# C-metr_analog.net
KiCad netlist of a schematic drawn in Altium Designer
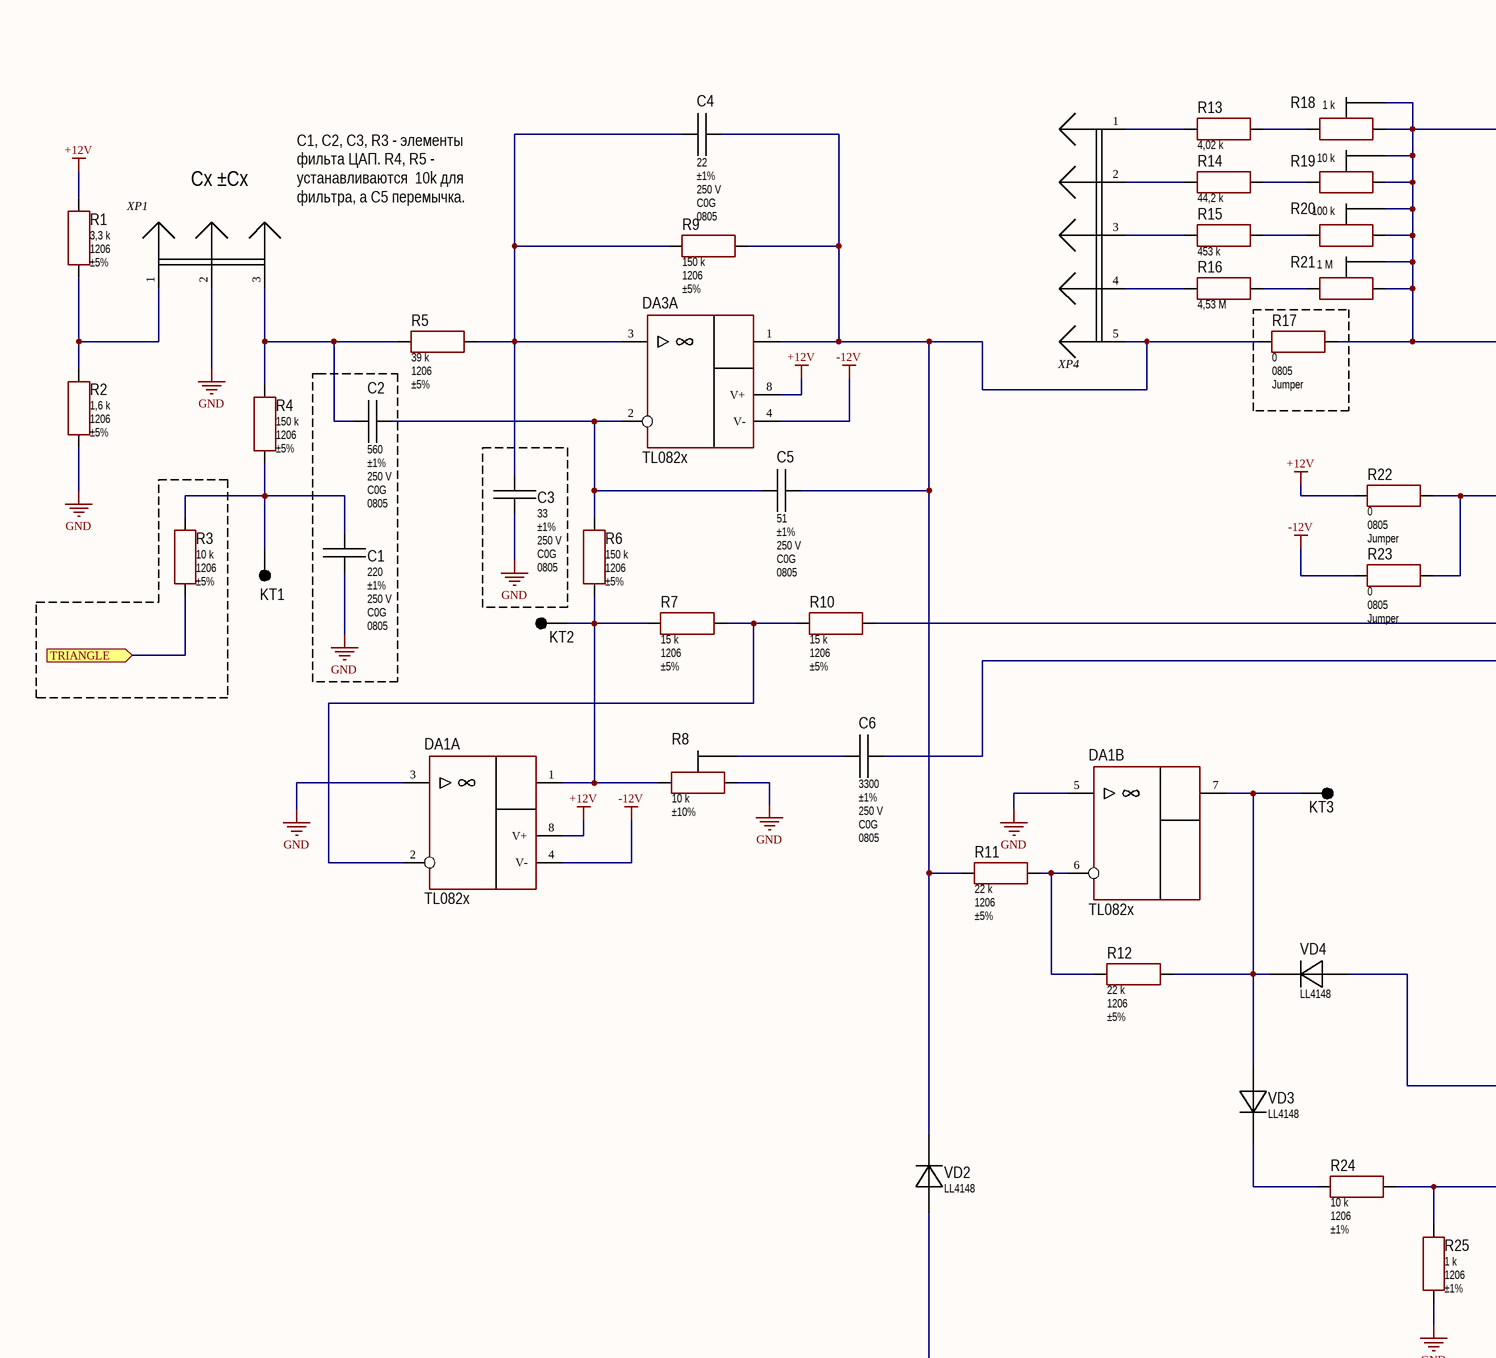
[diagram p0: C-metr_analog.SchDoc, top left]
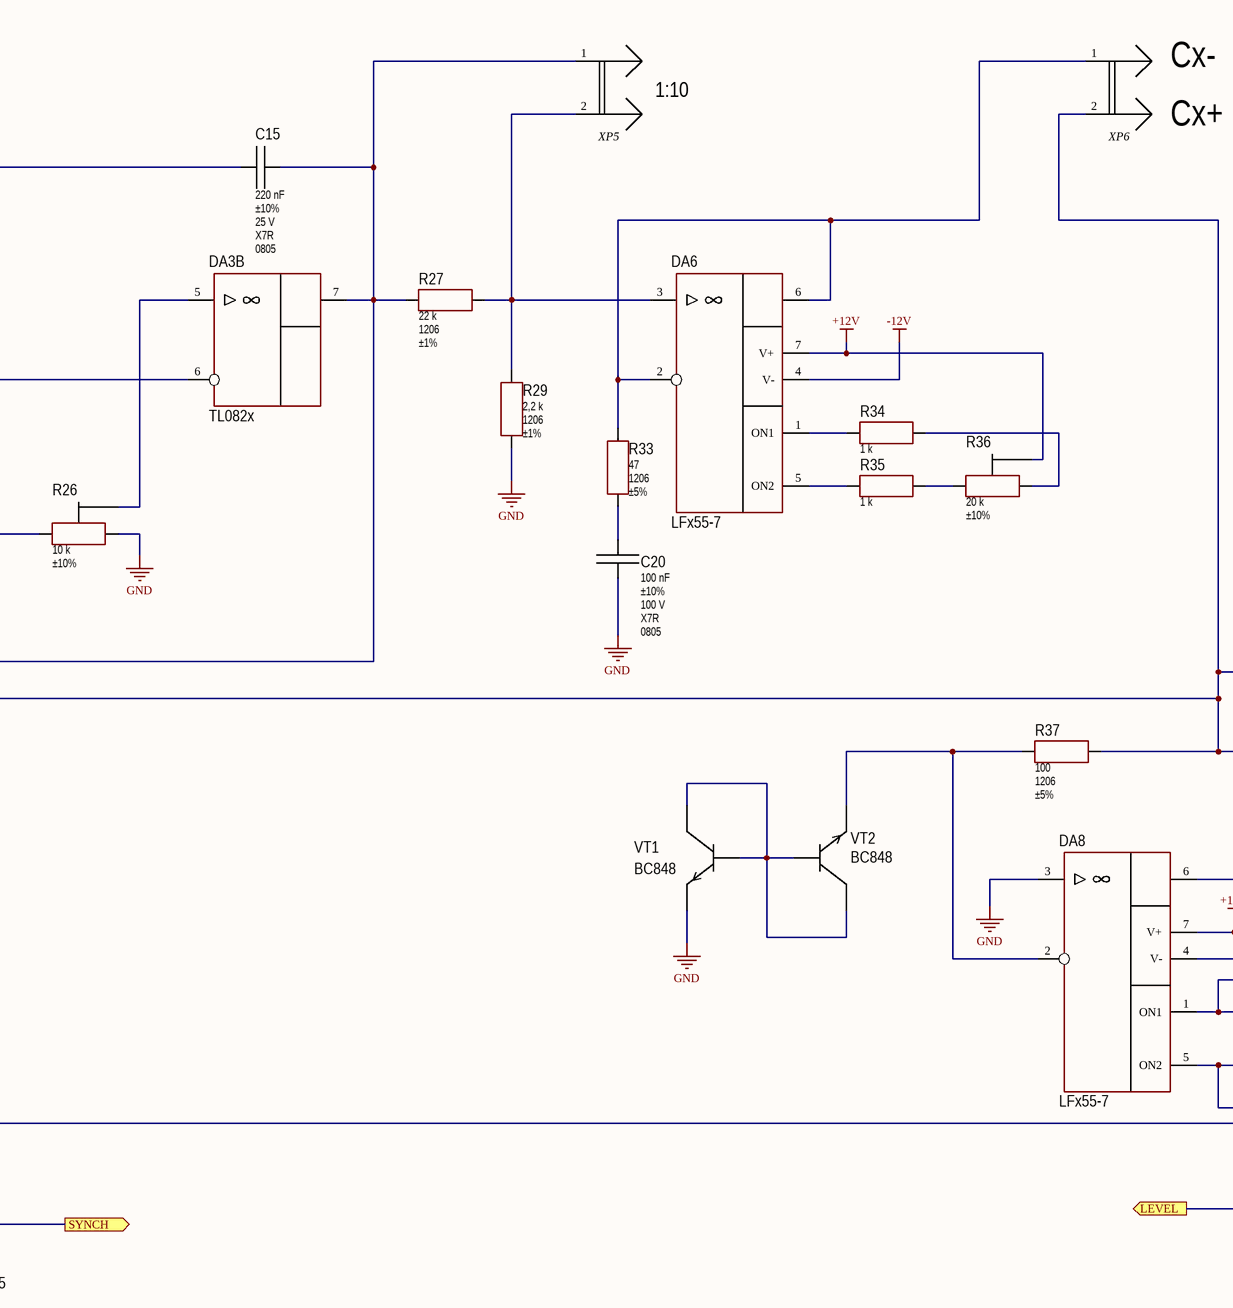
[diagram p1: C-metr_analog.SchDoc, top middle]
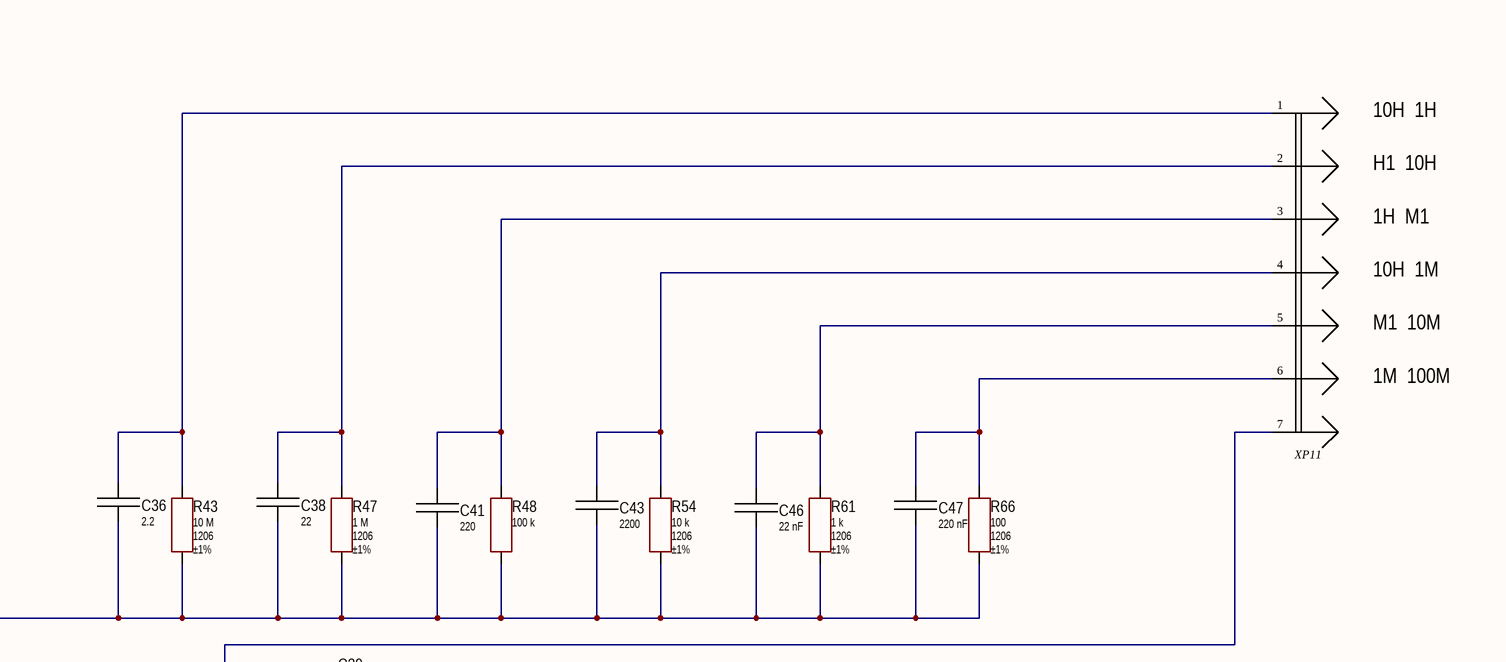
[diagram p2: C-metr_analog.SchDoc, top right]
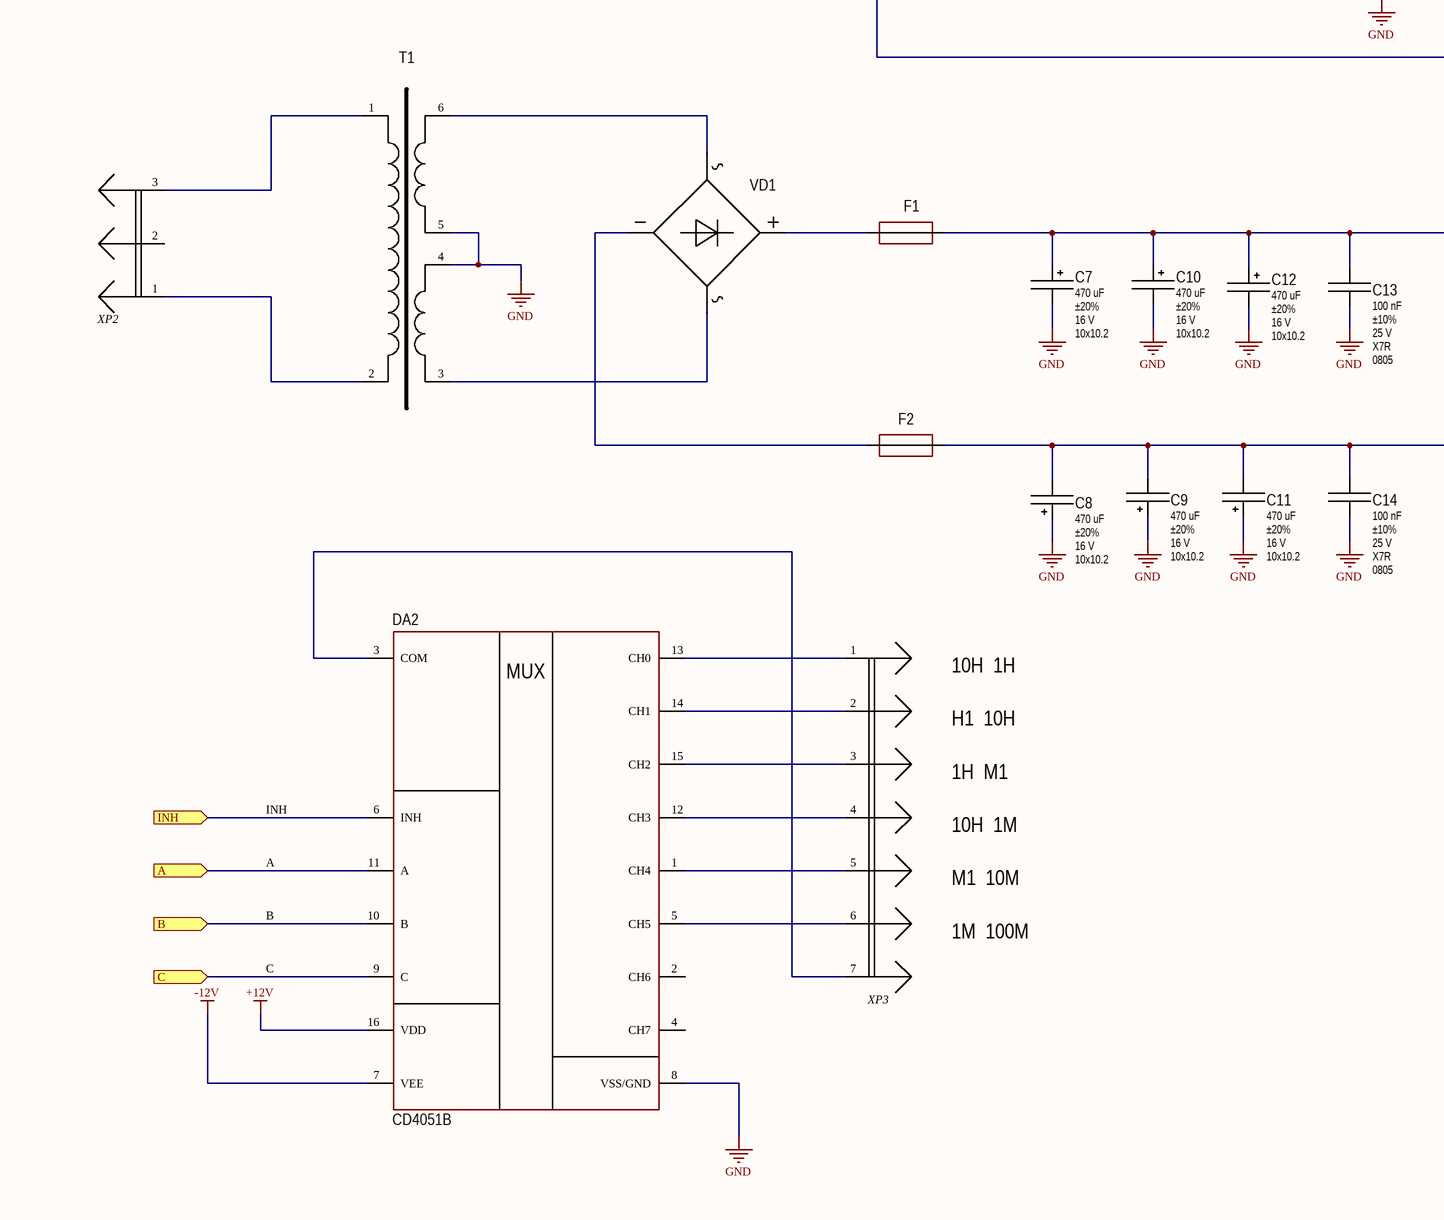
[diagram p3: C-metr_analog.SchDoc, bottom left]
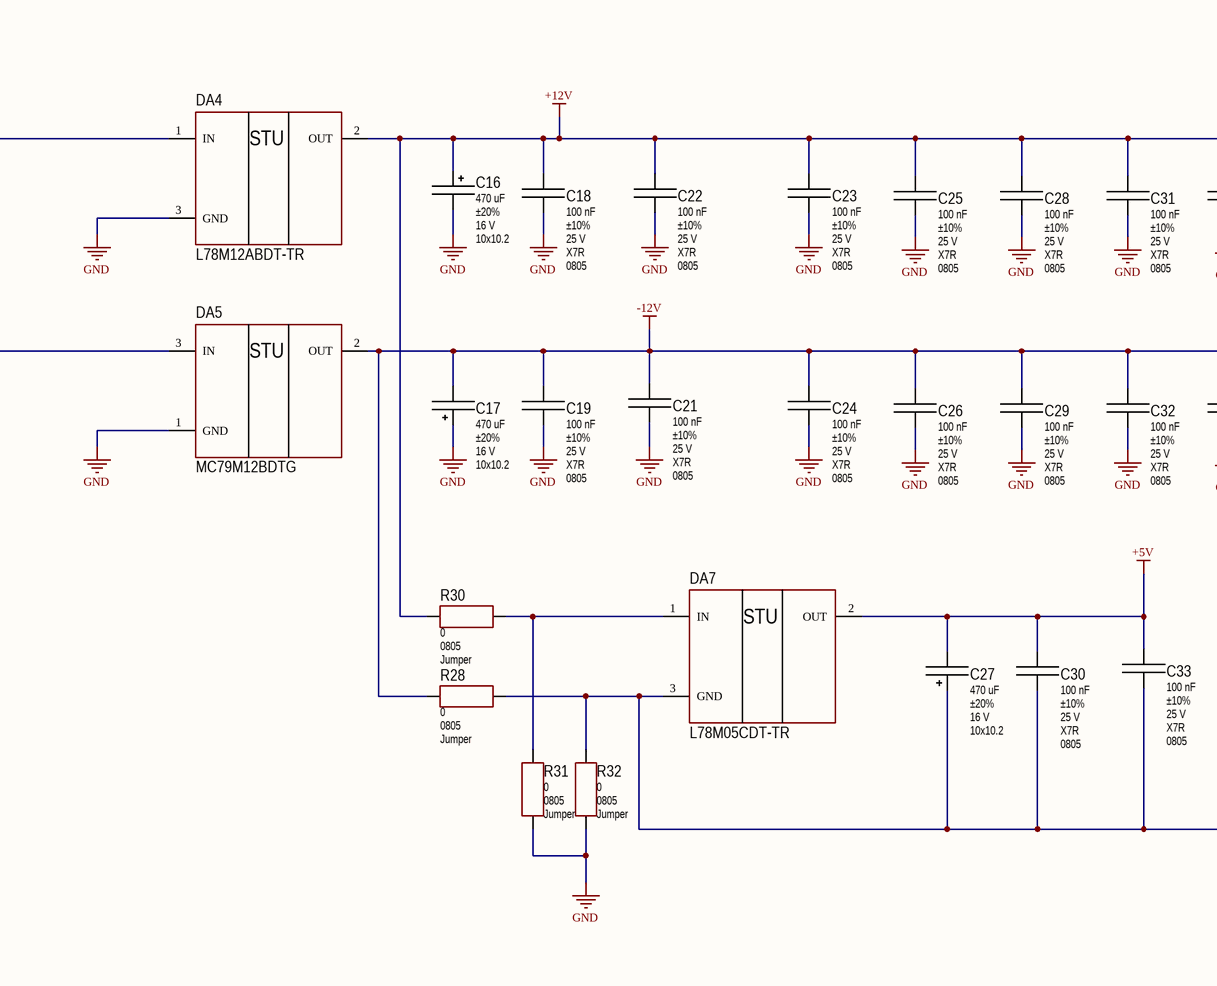
[diagram p4: C-metr_analog.SchDoc, bottom middle]
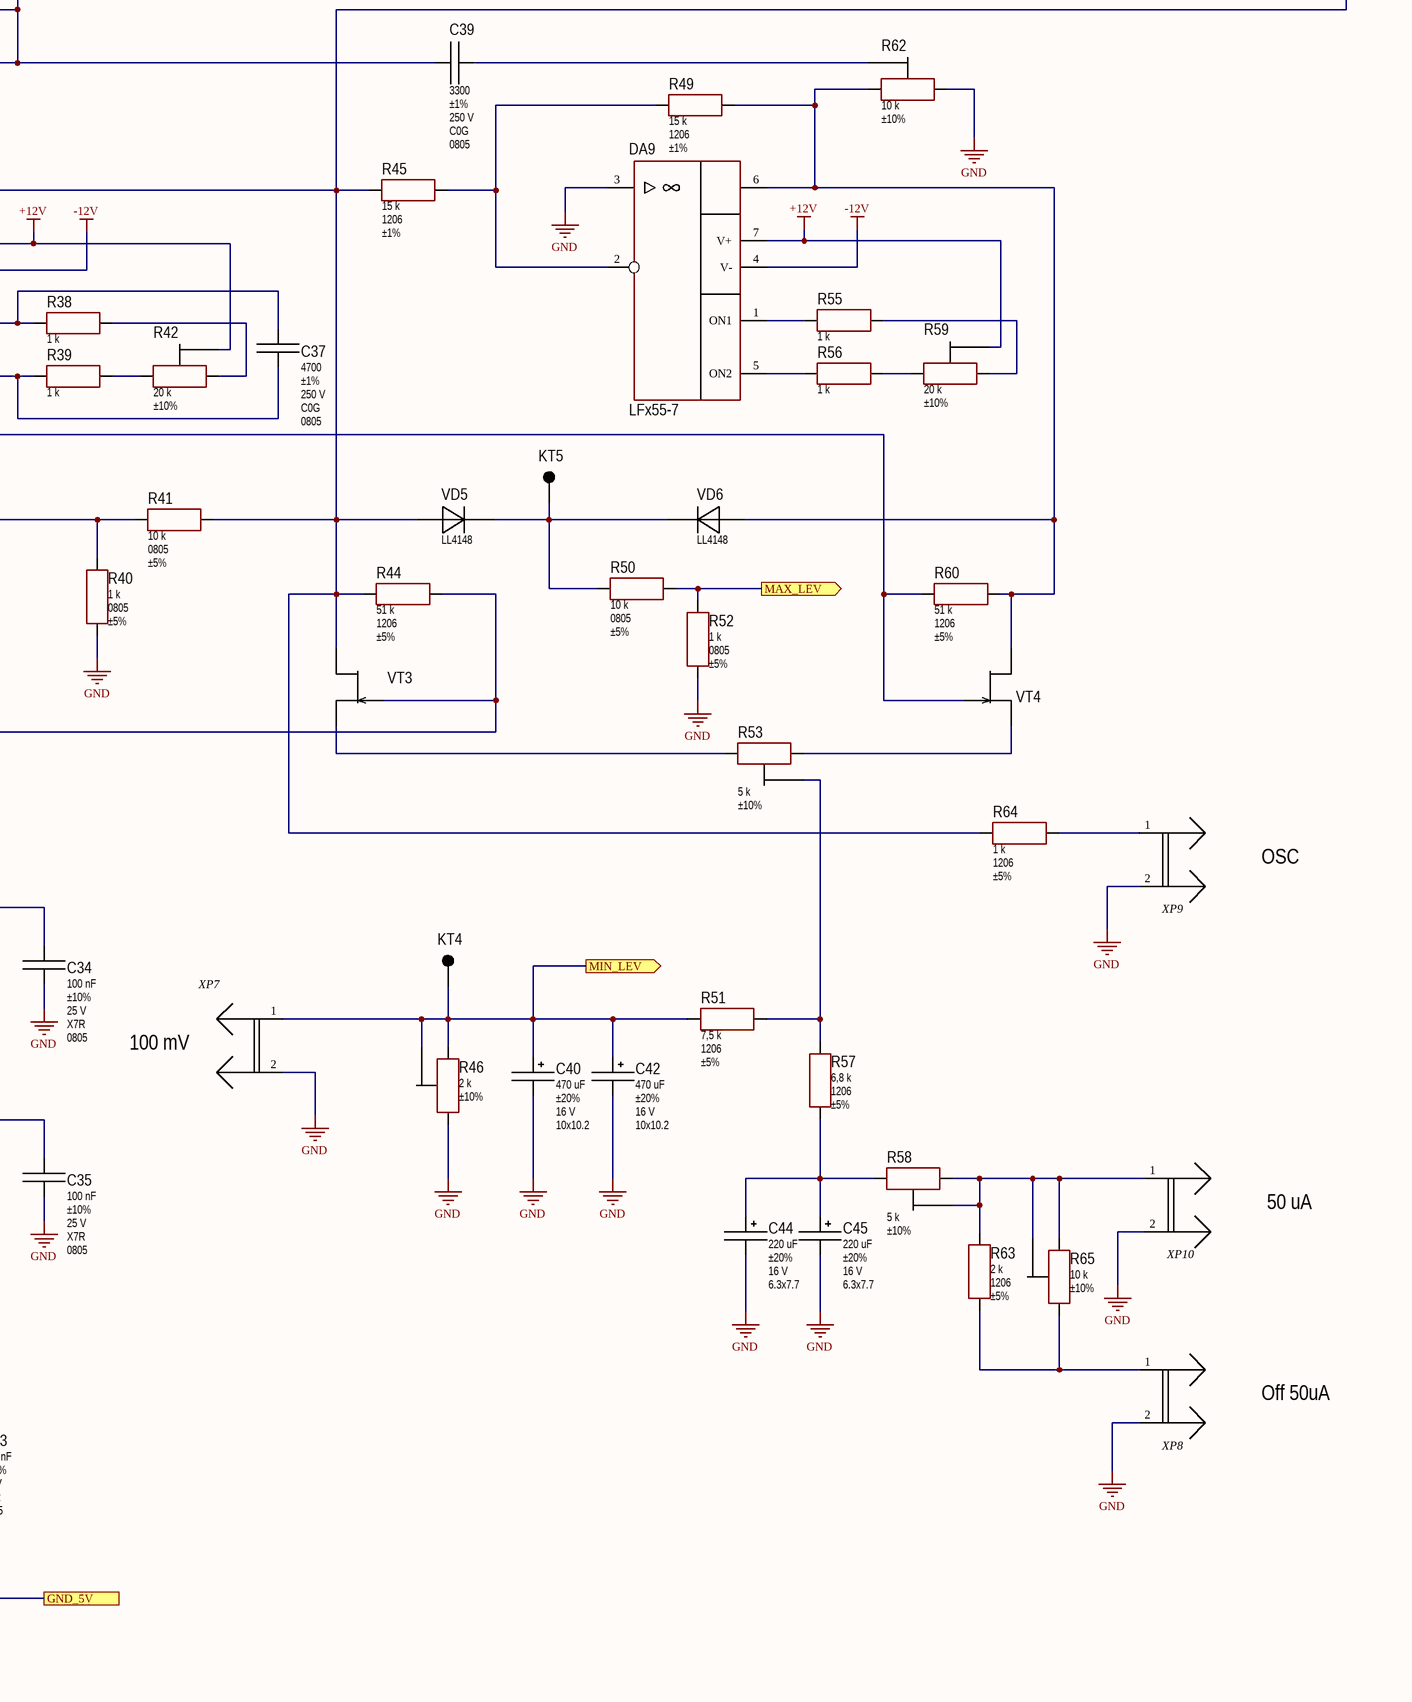
[diagram p5: C-metr_analog.SchDoc, bottom right]

(export (version "E")
  (design (tool "Eeschema 10.0.6"))
  (components
    (comp (ref "C1")
      (value "220")
      (footprint "C-0805-1.0")
      (fields
        (field (name "VALUESCH") "220")
        (field (name "TOLERANCE") "±1%")
        (field (name "VOLTAGE") "250 V")
        (field (name "DIELECTRIC") "C0G")
        (field (name "CASE") "0805")
        (field (name "PART NUMBER") "GRM21A5C2E221FW01D")
        (field (name "MANUFACTURER") "Murata Electronics")
      )
      (libsource (lib "GOST") (part "Capacitor"))
    )
    (comp (ref "C2")
      (value "560")
      (footprint "C-0805-1.0")
      (fields
        (field (name "VALUESCH") "560")
        (field (name "TOLERANCE") "±1%")
        (field (name "VOLTAGE") "250 V")
        (field (name "DIELECTRIC") "C0G")
        (field (name "CASE") "0805")
        (field (name "PART NUMBER") "GRM21A5C2E561FW01D")
        (field (name "MANUFACTURER") "Murata Electronics")
      )
      (libsource (lib "GOST") (part "Capacitor"))
    )
    (comp (ref "C3")
      (value "33")
      (footprint "C-0805-1.0")
      (fields
        (field (name "VALUESCH") "33")
        (field (name "TOLERANCE") "±1%")
        (field (name "VOLTAGE") "250 V")
        (field (name "DIELECTRIC") "C0G")
        (field (name "CASE") "0805")
        (field (name "PART NUMBER") "GRM21A5C2E330FW01D")
        (field (name "MANUFACTURER") "Murata Electronics")
      )
      (libsource (lib "GOST") (part "Capacitor"))
    )
    (comp (ref "C4")
      (value "22")
      (footprint "C-0805-1.0")
      (fields
        (field (name "VALUESCH") "22")
        (field (name "TOLERANCE") "±1%")
        (field (name "VOLTAGE") "250 V")
        (field (name "DIELECTRIC") "C0G")
        (field (name "CASE") "0805")
        (field (name "PART NUMBER") "GRM21A5C2E220FW01D")
        (field (name "MANUFACTURER") "Murata Electronics")
      )
      (libsource (lib "GOST") (part "Capacitor"))
    )
    (comp (ref "C5")
      (value "51")
      (footprint "C-0805-1.0")
      (fields
        (field (name "VALUESCH") "51")
        (field (name "TOLERANCE") "±1%")
        (field (name "VOLTAGE") "250 V")
        (field (name "DIELECTRIC") "C0G")
        (field (name "CASE") "0805")
        (field (name "PART NUMBER") "GRM21A5C2E151FW01D")
        (field (name "MANUFACTURER") "Murata Electronics")
      )
      (libsource (lib "GOST") (part "Capacitor"))
    )
    (comp (ref "C6")
      (value "3300")
      (footprint "C-0805-1.25")
      (fields
        (field (name "VALUESCH") "3300")
        (field (name "TOLERANCE") "±1%")
        (field (name "VOLTAGE") "250 V")
        (field (name "DIELECTRIC") "C0G")
        (field (name "CASE") "0805")
        (field (name "PART NUMBER") "GRM21B5C2E332FW01D")
        (field (name "MANUFACTURER") "Murata Electronics")
      )
      (libsource (lib "GOST") (part "Capacitor"))
    )
    (comp (ref "C7")
      (value "470 uF")
      (footprint "CAP-CASE G")
      (fields
        (field (name "TOLERANCE") "±20%")
        (field (name "VOLTAGE") "16 V")
        (field (name "CASE") "10x10.2")
        (field (name "PART NUMBER") "EEE-1CA471P")
        (field (name "MANUFACTURER") "Panasonic Electronic Components")
      )
      (libsource (lib "GOST") (part "Capacitor Polar"))
    )
    (comp (ref "C8")
      (value "470 uF")
      (footprint "CAP-CASE G")
      (fields
        (field (name "TOLERANCE") "±20%")
        (field (name "VOLTAGE") "16 V")
        (field (name "CASE") "10x10.2")
        (field (name "PART NUMBER") "EEE-1CA471P")
        (field (name "MANUFACTURER") "Panasonic Electronic Components")
      )
      (libsource (lib "GOST") (part "Capacitor Polar"))
    )
    (comp (ref "C9")
      (value "470 uF")
      (footprint "CAP-CASE G")
      (fields
        (field (name "TOLERANCE") "±20%")
        (field (name "VOLTAGE") "16 V")
        (field (name "CASE") "10x10.2")
        (field (name "PART NUMBER") "EEE-1CA471P")
        (field (name "MANUFACTURER") "Panasonic Electronic Components")
      )
      (libsource (lib "GOST") (part "Capacitor Polar"))
    )
    (comp (ref "C10")
      (value "470 uF")
      (footprint "CAP-CASE G")
      (fields
        (field (name "TOLERANCE") "±20%")
        (field (name "VOLTAGE") "16 V")
        (field (name "CASE") "10x10.2")
        (field (name "PART NUMBER") "EEE-1CA471P")
        (field (name "MANUFACTURER") "Panasonic Electronic Components")
      )
      (libsource (lib "GOST") (part "Capacitor Polar"))
    )
    (comp (ref "C11")
      (value "470 uF")
      (footprint "CAP-CASE G")
      (fields
        (field (name "TOLERANCE") "±20%")
        (field (name "VOLTAGE") "16 V")
        (field (name "CASE") "10x10.2")
        (field (name "PART NUMBER") "EEE-1CA471P")
        (field (name "MANUFACTURER") "Panasonic Electronic Components")
      )
      (libsource (lib "GOST") (part "Capacitor Polar"))
    )
    (comp (ref "C12")
      (value "470 uF")
      (footprint "CAP-CASE G")
      (fields
        (field (name "TOLERANCE") "±20%")
        (field (name "VOLTAGE") "16 V")
        (field (name "CASE") "10x10.2")
        (field (name "PART NUMBER") "EEE-1CA471P")
        (field (name "MANUFACTURER") "Panasonic Electronic Components")
      )
      (libsource (lib "GOST") (part "Capacitor Polar"))
    )
    (comp (ref "C13")
      (value "100 nF")
      (footprint "C-0805-0.95")
      (fields
        (field (name "VALUESCH") "100 nF")
        (field (name "TOLERANCE") "±10%")
        (field (name "VOLTAGE") "25 V")
        (field (name "DIELECTRIC") "X7R")
        (field (name "CASE") "0805")
        (field (name "PART NUMBER") "CC0805KRX7R8BB104")
        (field (name "MANUFACTURER") "Yageo")
      )
      (libsource (lib "GOST") (part "Capacitor"))
    )
    (comp (ref "C14")
      (value "100 nF")
      (footprint "C-0805-0.95")
      (fields
        (field (name "VALUESCH") "100 nF")
        (field (name "TOLERANCE") "±10%")
        (field (name "VOLTAGE") "25 V")
        (field (name "DIELECTRIC") "X7R")
        (field (name "CASE") "0805")
        (field (name "PART NUMBER") "CC0805KRX7R8BB104")
        (field (name "MANUFACTURER") "Yageo")
      )
      (libsource (lib "GOST") (part "Capacitor"))
    )
    (comp (ref "C15")
      (value "220 nF")
      (footprint "C-0805-0.95")
      (fields
        (field (name "VALUESCH") "220 nF")
        (field (name "TOLERANCE") "±10%")
        (field (name "VOLTAGE") "25 V")
        (field (name "DIELECTRIC") "X7R")
        (field (name "CASE") "0805")
        (field (name "PART NUMBER") "CC0805KRX7R8BB224")
        (field (name "MANUFACTURER") "Yageo")
      )
      (libsource (lib "GOST") (part "Capacitor"))
    )
    (comp (ref "C16")
      (value "470 uF")
      (footprint "CAP-CASE G")
      (fields
        (field (name "TOLERANCE") "±20%")
        (field (name "VOLTAGE") "16 V")
        (field (name "CASE") "10x10.2")
        (field (name "PART NUMBER") "EEE-1CA471P")
        (field (name "MANUFACTURER") "Panasonic Electronic Components")
      )
      (libsource (lib "GOST") (part "Capacitor Polar"))
    )
    (comp (ref "C17")
      (value "470 uF")
      (footprint "CAP-CASE G")
      (fields
        (field (name "TOLERANCE") "±20%")
        (field (name "VOLTAGE") "16 V")
        (field (name "CASE") "10x10.2")
        (field (name "PART NUMBER") "EEE-1CA471P")
        (field (name "MANUFACTURER") "Panasonic Electronic Components")
      )
      (libsource (lib "GOST") (part "Capacitor Polar"))
    )
    (comp (ref "C18")
      (value "100 nF")
      (footprint "C-0805-0.95")
      (fields
        (field (name "VALUESCH") "100 nF")
        (field (name "TOLERANCE") "±10%")
        (field (name "VOLTAGE") "25 V")
        (field (name "DIELECTRIC") "X7R")
        (field (name "CASE") "0805")
        (field (name "PART NUMBER") "CC0805KRX7R8BB104")
        (field (name "MANUFACTURER") "Yageo")
      )
      (libsource (lib "GOST") (part "Capacitor"))
    )
    (comp (ref "C19")
      (value "100 nF")
      (footprint "C-0805-0.95")
      (fields
        (field (name "VALUESCH") "100 nF")
        (field (name "TOLERANCE") "±10%")
        (field (name "VOLTAGE") "25 V")
        (field (name "DIELECTRIC") "X7R")
        (field (name "CASE") "0805")
        (field (name "PART NUMBER") "CC0805KRX7R8BB104")
        (field (name "MANUFACTURER") "Yageo")
      )
      (libsource (lib "GOST") (part "Capacitor"))
    )
    (comp (ref "C20")
      (value "100 nF")
      (footprint "C-0805-1.25")
      (fields
        (field (name "VALUESCH") "100 nF")
        (field (name "TOLERANCE") "±10%")
        (field (name "VOLTAGE") "100 V")
        (field (name "DIELECTRIC") "X7R")
        (field (name "CASE") "0805")
        (field (name "PART NUMBER") "GCM21BR72A104KA37L")
        (field (name "MANUFACTURER") "Murata Electronics")
      )
      (libsource (lib "GOST") (part "Capacitor"))
    )
    (comp (ref "C21")
      (value "100 nF")
      (footprint "C-0805-0.95")
      (fields
        (field (name "VALUESCH") "100 nF")
        (field (name "TOLERANCE") "±10%")
        (field (name "VOLTAGE") "25 V")
        (field (name "DIELECTRIC") "X7R")
        (field (name "CASE") "0805")
        (field (name "PART NUMBER") "CC0805KRX7R8BB104")
        (field (name "MANUFACTURER") "Yageo")
      )
      (libsource (lib "GOST") (part "Capacitor"))
    )
    (comp (ref "C22")
      (value "100 nF")
      (footprint "C-0805-0.95")
      (fields
        (field (name "VALUESCH") "100 nF")
        (field (name "TOLERANCE") "±10%")
        (field (name "VOLTAGE") "25 V")
        (field (name "DIELECTRIC") "X7R")
        (field (name "CASE") "0805")
        (field (name "PART NUMBER") "CC0805KRX7R8BB104")
        (field (name "MANUFACTURER") "Yageo")
      )
      (libsource (lib "GOST") (part "Capacitor"))
    )
    (comp (ref "C23")
      (value "100 nF")
      (footprint "C-0805-0.95")
      (fields
        (field (name "VALUESCH") "100 nF")
        (field (name "TOLERANCE") "±10%")
        (field (name "VOLTAGE") "25 V")
        (field (name "DIELECTRIC") "X7R")
        (field (name "CASE") "0805")
        (field (name "PART NUMBER") "CC0805KRX7R8BB104")
        (field (name "MANUFACTURER") "Yageo")
      )
      (libsource (lib "GOST") (part "Capacitor"))
    )
    (comp (ref "C24")
      (value "100 nF")
      (footprint "C-0805-0.95")
      (fields
        (field (name "VALUESCH") "100 nF")
        (field (name "TOLERANCE") "±10%")
        (field (name "VOLTAGE") "25 V")
        (field (name "DIELECTRIC") "X7R")
        (field (name "CASE") "0805")
        (field (name "PART NUMBER") "CC0805KRX7R8BB104")
        (field (name "MANUFACTURER") "Yageo")
      )
      (libsource (lib "GOST") (part "Capacitor"))
    )
    (comp (ref "C25")
      (value "100 nF")
      (footprint "C-0805-0.95")
      (fields
        (field (name "VALUESCH") "100 nF")
        (field (name "TOLERANCE") "±10%")
        (field (name "VOLTAGE") "25 V")
        (field (name "DIELECTRIC") "X7R")
        (field (name "CASE") "0805")
        (field (name "PART NUMBER") "CC0805KRX7R8BB104")
        (field (name "MANUFACTURER") "Yageo")
      )
      (libsource (lib "GOST") (part "Capacitor"))
    )
    (comp (ref "C26")
      (value "100 nF")
      (footprint "C-0805-0.95")
      (fields
        (field (name "VALUESCH") "100 nF")
        (field (name "TOLERANCE") "±10%")
        (field (name "VOLTAGE") "25 V")
        (field (name "DIELECTRIC") "X7R")
        (field (name "CASE") "0805")
        (field (name "PART NUMBER") "CC0805KRX7R8BB104")
        (field (name "MANUFACTURER") "Yageo")
      )
      (libsource (lib "GOST") (part "Capacitor"))
    )
    (comp (ref "C27")
      (value "470 uF")
      (footprint "CAP-CASE G")
      (fields
        (field (name "TOLERANCE") "±20%")
        (field (name "VOLTAGE") "16 V")
        (field (name "CASE") "10x10.2")
        (field (name "PART NUMBER") "EEE-1CA471P")
        (field (name "MANUFACTURER") "Panasonic Electronic Components")
      )
      (libsource (lib "GOST") (part "Capacitor Polar"))
    )
    (comp (ref "C28")
      (value "100 nF")
      (footprint "C-0805-0.95")
      (fields
        (field (name "VALUESCH") "100 nF")
        (field (name "TOLERANCE") "±10%")
        (field (name "VOLTAGE") "25 V")
        (field (name "DIELECTRIC") "X7R")
        (field (name "CASE") "0805")
        (field (name "PART NUMBER") "CC0805KRX7R8BB104")
        (field (name "MANUFACTURER") "Yageo")
      )
      (libsource (lib "GOST") (part "Capacitor"))
    )
    (comp (ref "C29")
      (value "100 nF")
      (footprint "C-0805-0.95")
      (fields
        (field (name "VALUESCH") "100 nF")
        (field (name "TOLERANCE") "±10%")
        (field (name "VOLTAGE") "25 V")
        (field (name "DIELECTRIC") "X7R")
        (field (name "CASE") "0805")
        (field (name "PART NUMBER") "CC0805KRX7R8BB104")
        (field (name "MANUFACTURER") "Yageo")
      )
      (libsource (lib "GOST") (part "Capacitor"))
    )
    (comp (ref "C30")
      (value "100 nF")
      (footprint "C-0805-0.95")
      (fields
        (field (name "VALUESCH") "100 nF")
        (field (name "TOLERANCE") "±10%")
        (field (name "VOLTAGE") "25 V")
        (field (name "DIELECTRIC") "X7R")
        (field (name "CASE") "0805")
        (field (name "PART NUMBER") "CC0805KRX7R8BB104")
        (field (name "MANUFACTURER") "Yageo")
      )
      (libsource (lib "GOST") (part "Capacitor"))
    )
    (comp (ref "C31")
      (value "100 nF")
      (footprint "C-0805-0.95")
      (fields
        (field (name "VALUESCH") "100 nF")
        (field (name "TOLERANCE") "±10%")
        (field (name "VOLTAGE") "25 V")
        (field (name "DIELECTRIC") "X7R")
        (field (name "CASE") "0805")
        (field (name "PART NUMBER") "CC0805KRX7R8BB104")
        (field (name "MANUFACTURER") "Yageo")
      )
      (libsource (lib "GOST") (part "Capacitor"))
    )
    (comp (ref "C32")
      (value "100 nF")
      (footprint "C-0805-0.95")
      (fields
        (field (name "VALUESCH") "100 nF")
        (field (name "TOLERANCE") "±10%")
        (field (name "VOLTAGE") "25 V")
        (field (name "DIELECTRIC") "X7R")
        (field (name "CASE") "0805")
        (field (name "PART NUMBER") "CC0805KRX7R8BB104")
        (field (name "MANUFACTURER") "Yageo")
      )
      (libsource (lib "GOST") (part "Capacitor"))
    )
    (comp (ref "C33")
      (value "100 nF")
      (footprint "C-0805-0.95")
      (fields
        (field (name "VALUESCH") "100 nF")
        (field (name "TOLERANCE") "±10%")
        (field (name "VOLTAGE") "25 V")
        (field (name "DIELECTRIC") "X7R")
        (field (name "CASE") "0805")
        (field (name "PART NUMBER") "CC0805KRX7R8BB104")
        (field (name "MANUFACTURER") "Yageo")
      )
      (libsource (lib "GOST") (part "Capacitor"))
    )
    (comp (ref "C34")
      (value "100 nF")
      (footprint "C-0805-0.95")
      (fields
        (field (name "VALUESCH") "100 nF")
        (field (name "TOLERANCE") "±10%")
        (field (name "VOLTAGE") "25 V")
        (field (name "DIELECTRIC") "X7R")
        (field (name "CASE") "0805")
        (field (name "PART NUMBER") "CC0805KRX7R8BB104")
        (field (name "MANUFACTURER") "Yageo")
      )
      (libsource (lib "GOST") (part "Capacitor"))
    )
    (comp (ref "C35")
      (value "100 nF")
      (footprint "C-0805-0.95")
      (fields
        (field (name "VALUESCH") "100 nF")
        (field (name "TOLERANCE") "±10%")
        (field (name "VOLTAGE") "25 V")
        (field (name "DIELECTRIC") "X7R")
        (field (name "CASE") "0805")
        (field (name "PART NUMBER") "CC0805KRX7R8BB104")
        (field (name "MANUFACTURER") "Yageo")
      )
      (libsource (lib "GOST") (part "Capacitor"))
    )
    (comp (ref "C36")
      (value "2.2")
      (footprint "C-0805-1.0")
      (fields
        (field (name "VALUESCH") "2.2")
        (field (name "TOLERANCE") "±1%")
        (field (name "VOLTAGE") "250 V")
        (field (name "PART NUMBER") "GRM21A5C2E220FW01D")
      )
      (libsource (lib "GOST") (part "Capacitor"))
    )
    (comp (ref "C37")
      (value "4700")
      (footprint "C-0805-1.25")
      (fields
        (field (name "VALUESCH") "4700")
        (field (name "TOLERANCE") "±1%")
        (field (name "VOLTAGE") "250 V")
        (field (name "DIELECTRIC") "C0G")
        (field (name "CASE") "0805")
        (field (name "PART NUMBER") "GRM21B5C2E472FW01D")
        (field (name "MANUFACTURER") "Murata Electronics")
      )
      (libsource (lib "GOST") (part "Capacitor"))
    )
    (comp (ref "C38")
      (value "22")
      (footprint "C-0805-1.0")
      (fields
        (field (name "VALUESCH") "22")
        (field (name "TOLERANCE") "±1%")
        (field (name "VOLTAGE") "250 V")
        (field (name "PART NUMBER") "GRM21A5C2E220FW01D")
      )
      (libsource (lib "GOST") (part "Capacitor"))
    )
    (comp (ref "C39")
      (value "3300")
      (footprint "C-0805-1.25")
      (fields
        (field (name "VALUESCH") "3300")
        (field (name "TOLERANCE") "±1%")
        (field (name "VOLTAGE") "250 V")
        (field (name "DIELECTRIC") "C0G")
        (field (name "CASE") "0805")
        (field (name "PART NUMBER") "GRM21B5C2E332FW01D")
        (field (name "MANUFACTURER") "Murata Electronics")
      )
      (libsource (lib "GOST") (part "Capacitor"))
    )
    (comp (ref "C40")
      (value "470 uF")
      (footprint "CAP-CASE G")
      (fields
        (field (name "TOLERANCE") "±20%")
        (field (name "VOLTAGE") "16 V")
        (field (name "CASE") "10x10.2")
        (field (name "PART NUMBER") "EEE-1CA471P")
        (field (name "MANUFACTURER") "Panasonic Electronic Components")
      )
      (libsource (lib "GOST") (part "Capacitor Polar"))
    )
    (comp (ref "C41")
      (value "220")
      (footprint "C-0805-1.0")
      (fields
        (field (name "VALUESCH") "220")
        (field (name "TOLERANCE") "±1%")
        (field (name "VOLTAGE") "250 V")
        (field (name "PART NUMBER") "GRM21A5C2E221FW01D")
      )
      (libsource (lib "GOST") (part "Capacitor"))
    )
    (comp (ref "C42")
      (value "470 uF")
      (footprint "CAP-CASE G")
      (fields
        (field (name "TOLERANCE") "±20%")
        (field (name "VOLTAGE") "16 V")
        (field (name "CASE") "10x10.2")
        (field (name "PART NUMBER") "EEE-1CA471P")
        (field (name "MANUFACTURER") "Panasonic Electronic Components")
      )
      (libsource (lib "GOST") (part "Capacitor Polar"))
    )
    (comp (ref "C43")
      (value "2200")
      (footprint "C-0805-1.0")
      (fields
        (field (name "VALUESCH") "2200")
        (field (name "TOLERANCE") "±1%")
        (field (name "VOLTAGE") "250 V")
        (field (name "PART NUMBER") "GRM21A5C2E222FW01D")
      )
      (libsource (lib "GOST") (part "Capacitor"))
    )
    (comp (ref "C44")
      (value "220 uF")
      (footprint "CAP-CASE D8")
      (fields
        (field (name "TOLERANCE") "±20%")
        (field (name "VOLTAGE") "16 V")
        (field (name "CASE") "6.3x7.7")
        (field (name "PART NUMBER") "EEE-1CA221XP")
        (field (name "MANUFACTURER") "Panasonic Electronic Components")
      )
      (libsource (lib "GOST") (part "Capacitor Polar"))
    )
    (comp (ref "C45")
      (value "220 uF")
      (footprint "CAP-CASE D8")
      (fields
        (field (name "TOLERANCE") "±20%")
        (field (name "VOLTAGE") "16 V")
        (field (name "CASE") "6.3x7.7")
        (field (name "PART NUMBER") "EEE-1CA221XP")
        (field (name "MANUFACTURER") "Panasonic Electronic Components")
      )
      (libsource (lib "GOST") (part "Capacitor Polar"))
    )
    (comp (ref "C46")
      (value "22 nF")
      (footprint "C-0805-1.25")
      (fields
        (field (name "VALUESCH") "22 nF")
        (field (name "TOLERANCE") "±5%")
        (field (name "VOLTAGE") "50 V")
        (field (name "PART NUMBER") "GCM21B5C1H223JA16L")
      )
      (libsource (lib "GOST") (part "Capacitor"))
    )
    (comp (ref "C47")
      (value "220 nF")
      (footprint "C-0805-0.95")
      (fields
        (field (name "VALUESCH") "220 nF")
        (field (name "TOLERANCE") "±10%")
        (field (name "VOLTAGE") "25 V")
        (field (name "PART NUMBER") "CC0805KRX7R8BB224")
      )
      (libsource (lib "GOST") (part "Capacitor"))
    )
    (comp (ref "DA1")
      (value "TL082x")
      (footprint "DIP-8")
      (description "IC OPAMP FET-Input SOIC-8")
      (fields (field (name "PART NUMBER") "TL062CN") (field (name "MANUFACTURER") "STMicroelectronics"))
      (libsource (lib "GOST") (part "TL062x"))
    )
    (comp (ref "DA2")
      (value "CD4051B")
      (footprint "SOIC-16")
      (fields (field (name "PART NUMBER") "CD4051BM") (field (name "MANUFACTURER") "Texas  Instruments"))
      (libsource (lib "GOST") (part "CD4051B"))
    )
    (comp (ref "DA3")
      (value "TL082x")
      (footprint "DIP-8")
      (description "IC OPAMP FET-Input SOIC-8")
      (fields (field (name "PART NUMBER") "TL062CN") (field (name "MANUFACTURER") "STMicroelectronics"))
      (libsource (lib "GOST") (part "TL062x"))
    )
    (comp (ref "DA4")
      (value "L78M12ABDT-TR")
      (footprint "DPAK")
      (description "IC REG LINEAR")
      (fields (field (name "MANUFACTURER") "STMicroelectronics"))
      (libsource (lib "GOST") (part "L78Mxx"))
    )
    (comp (ref "DA5")
      (value "MC79M12BDTG")
      (footprint "DPAK")
      (description "IC REG LINEAR")
      (libsource (lib "GOST") (part "L79Mxx"))
    )
    (comp (ref "DA6")
      (value "LFx55-7")
      (footprint "DIP-8")
      (fields (field (name "PART NUMBER") "LF357N") (field (name "MANUFACTURER") "STMicroelectronics"))
      (libsource (lib "GOST") (part "LFx55-7"))
    )
    (comp (ref "DA7")
      (value "L78M05CDT-TR")
      (footprint "DPAK")
      (description "IC REG LINEAR")
      (fields (field (name "MANUFACTURER") "STMicroelectronics"))
      (libsource (lib "GOST") (part "L78Mxx"))
    )
    (comp (ref "DA8")
      (value "LFx55-7")
      (footprint "DIP-8")
      (fields (field (name "PART NUMBER") "LF357N") (field (name "MANUFACTURER") "STMicroelectronics"))
      (libsource (lib "GOST") (part "LFx55-7"))
    )
    (comp (ref "DA9")
      (value "LFx55-7")
      (footprint "DIP-8")
      (fields (field (name "PART NUMBER") "LF357N") (field (name "MANUFACTURER") "STMicroelectronics"))
      (libsource (lib "GOST") (part "LFx55-7"))
    )
    (comp (ref "F1")
      (value "Fuse")
      (footprint "F-0805")
      (fields
        (field (name "PART NUMBER") "SMD0805P05TF")
        (field (name "MANUFACTURER") "Shenzhen Ruilongyuan Electronics Co., Ttd (RUILON)")
      )
      (libsource (lib "GOST") (part "Fuse"))
    )
    (comp (ref "F2")
      (value "Fuse")
      (footprint "F-0805")
      (fields
        (field (name "PART NUMBER") "SMD0805P05TF")
        (field (name "MANUFACTURER") "Shenzhen Ruilongyuan Electronics Co., Ttd (RUILON)")
      )
      (libsource (lib "GOST") (part "Fuse"))
    )
    (comp (ref "KT1")
      (value "Лепесток 2-1,2-3,0-7-Л63-07")
      (footprint "AGE.271441.002-05")
      (libsource (lib "GOST") (part "Lepestok"))
    )
    (comp (ref "KT2")
      (value "Лепесток 2-1,2-3,0-7-Л63-07")
      (footprint "AGE.271441.002-05")
      (libsource (lib "GOST") (part "Lepestok"))
    )
    (comp (ref "KT3")
      (value "Лепесток 2-1,2-3,0-7-Л63-07")
      (footprint "AGE.271441.002-05")
      (libsource (lib "GOST") (part "Lepestok"))
    )
    (comp (ref "KT4")
      (value "Лепесток 2-1,2-3,0-7-Л63-07")
      (footprint "AGE.271441.002-05")
      (libsource (lib "GOST") (part "Lepestok"))
    )
    (comp (ref "KT5")
      (value "Лепесток 2-1,2-3,0-7-Л63-07")
      (footprint "AGE.271441.002-05")
      (libsource (lib "GOST") (part "Lepestok"))
    )
    (comp (ref "R1")
      (value "3,3 k")
      (footprint "R-1206")
      (fields
        (field (name "VALUESCH") "3,3 k")
        (field (name "CASE") "1206")
        (field (name "TOLERANCE") "±5%")
        (field (name "PART NUMBER") "CRCW12063K30JNEA")
        (field (name "POWER") "0,25 W")
        (field (name "MANUFACTURER") "Vishay Dale")
      )
      (libsource (lib "GOST") (part "Resistor"))
    )
    (comp (ref "R2")
      (value "1,6 k")
      (footprint "R-1206")
      (fields
        (field (name "VALUESCH") "1,6 k")
        (field (name "CASE") "1206")
        (field (name "TOLERANCE") "±5%")
        (field (name "PART NUMBER") "CRCW12061K60JNEA")
        (field (name "POWER") "0,25 W")
        (field (name "MANUFACTURER") "Vishay Dale")
      )
      (libsource (lib "") (part "Resistor_2"))
    )
    (comp (ref "R3")
      (value "10 k")
      (footprint "R-1206")
      (fields
        (field (name "VALUESCH") "10 k")
        (field (name "CASE") "1206")
        (field (name "TOLERANCE") "±5%")
        (field (name "PART NUMBER") "CRCW120610K0JNEA")
        (field (name "POWER") "0,25 W")
        (field (name "MANUFACTURER") "Vishay Dale")
      )
      (libsource (lib "") (part "Resistor_2"))
    )
    (comp (ref "R4")
      (value "150 k")
      (footprint "R-1206")
      (fields
        (field (name "VALUESCH") "150 k")
        (field (name "CASE") "1206")
        (field (name "TOLERANCE") "±5%")
        (field (name "PART NUMBER") "CRCW1206150KJNEA")
        (field (name "POWER") "0,25 W")
        (field (name "MANUFACTURER") "Vishay Dale")
      )
      (libsource (lib "GOST") (part "Resistor"))
    )
    (comp (ref "R5")
      (value "39 k")
      (footprint "R-1206")
      (fields
        (field (name "VALUESCH") "39 k")
        (field (name "CASE") "1206")
        (field (name "TOLERANCE") "±5%")
        (field (name "PART NUMBER") "CRCW120639K0JNEA")
        (field (name "POWER") "0,25 W")
        (field (name "MANUFACTURER") "Vishay Dale")
      )
      (libsource (lib "") (part "Resistor_1"))
    )
    (comp (ref "R6")
      (value "150 k")
      (footprint "R-1206")
      (fields
        (field (name "VALUESCH") "150 k")
        (field (name "CASE") "1206")
        (field (name "TOLERANCE") "±5%")
        (field (name "PART NUMBER") "CRCW1206150KJNEA")
        (field (name "POWER") "0,25 W")
        (field (name "MANUFACTURER") "Vishay Dale")
      )
      (libsource (lib "GOST") (part "Resistor"))
    )
    (comp (ref "R7")
      (value "15 k")
      (footprint "R-1206")
      (fields
        (field (name "VALUESCH") "15 k")
        (field (name "CASE") "1206")
        (field (name "TOLERANCE") "±5%")
        (field (name "PART NUMBER") "CRCW120615K0JNEA")
        (field (name "POWER") "0,25 W")
        (field (name "MANUFACTURER") "Vishay Dale")
      )
      (libsource (lib "") (part "Resistor_1"))
    )
    (comp (ref "R8")
      (value "10 k")
      (footprint "3296W")
      (fields
        (field (name "VALUESCH") "10 k")
        (field (name "TOLERANCE") "±10%")
        (field (name "PART NUMBER") "3296W-1-103LF")
        (field (name "POWER") "0,5 W")
        (field (name "MANUFACTURER") "Bourns Inc.")
      )
      (libsource (lib "") (part "Resistor-ADJ_1"))
    )
    (comp (ref "R9")
      (value "150 k")
      (footprint "R-1206")
      (fields
        (field (name "VALUESCH") "150 k")
        (field (name "CASE") "1206")
        (field (name "TOLERANCE") "±5%")
        (field (name "PART NUMBER") "CRCW1206150KJNEA")
        (field (name "POWER") "0,25 W")
        (field (name "MANUFACTURER") "Vishay Dale")
      )
      (libsource (lib "") (part "Resistor_1"))
    )
    (comp (ref "R10")
      (value "15 k")
      (footprint "R-1206")
      (fields
        (field (name "VALUESCH") "15 k")
        (field (name "CASE") "1206")
        (field (name "TOLERANCE") "±5%")
        (field (name "PART NUMBER") "CRCW120615K0JNEA")
        (field (name "POWER") "0,25 W")
        (field (name "MANUFACTURER") "Vishay Dale")
      )
      (libsource (lib "") (part "Resistor_1"))
    )
    (comp (ref "R11")
      (value "22 k")
      (footprint "R-1206")
      (fields
        (field (name "VALUESCH") "22 k")
        (field (name "CASE") "1206")
        (field (name "TOLERANCE") "±5%")
        (field (name "PART NUMBER") "CRCW120622K0JNEA")
        (field (name "POWER") "0,25 W")
        (field (name "MANUFACTURER") "Vishay Dale")
      )
      (libsource (lib "") (part "Resistor_1"))
    )
    (comp (ref "R12")
      (value "22 k")
      (footprint "R-1206")
      (fields
        (field (name "VALUESCH") "22 k")
        (field (name "CASE") "1206")
        (field (name "TOLERANCE") "±5%")
        (field (name "PART NUMBER") "CRCW120622K0JNEA")
        (field (name "POWER") "0,25 W")
        (field (name "MANUFACTURER") "Vishay Dale")
      )
      (libsource (lib "") (part "Resistor_1"))
    )
    (comp (ref "R13")
      (value "4,02 k")
      (footprint "R-1206")
      (fields
        (field (name "VALUESCH") "4,02 k")
        (field (name "TOLERANCE") "±1%")
        (field (name "PART NUMBER") "CRCW12064K02FKEA")
        (field (name "POWER") "0,25 W")
      )
      (libsource (lib "") (part "Resistor_1"))
    )
    (comp (ref "R14")
      (value "44,2 k")
      (footprint "R-1206")
      (fields
        (field (name "VALUESCH") "44,2 k")
        (field (name "TOLERANCE") "±1%")
        (field (name "PART NUMBER") "CRCW120644K2FKEA")
        (field (name "POWER") "0,25 W")
      )
      (libsource (lib "") (part "Resistor_1"))
    )
    (comp (ref "R15")
      (value "453 k")
      (footprint "R-1206")
      (fields
        (field (name "VALUESCH") "453 k")
        (field (name "TOLERANCE") "±1%")
        (field (name "PART NUMBER") "CRCW1206453KFKEA")
        (field (name "POWER") "0,25 W")
      )
      (libsource (lib "") (part "Resistor_1"))
    )
    (comp (ref "R16")
      (value "4,53 M")
      (footprint "R-1206")
      (fields
        (field (name "VALUESCH") "4,53 M")
        (field (name "TOLERANCE") "±1%")
        (field (name "PART NUMBER") "CRCW12064M53FKEA")
        (field (name "POWER") "0,25 W")
      )
      (libsource (lib "") (part "Resistor_1"))
    )
    (comp (ref "R17")
      (value "0")
      (footprint "R-0805")
      (fields
        (field (name "VALUESCH") "0")
        (field (name "CASE") "0805")
        (field (name "TOLERANCE") "Jumper")
        (field (name "PART NUMBER") "CRCW08050000Z0EA")
        (field (name "POWER") "0,125 W")
        (field (name "MANUFACTURER") "Vishay Dale")
      )
      (libsource (lib "") (part "Resistor_1"))
    )
    (comp (ref "R18")
      (value "1 k")
      (footprint "3296W")
      (fields
        (field (name "VALUESCH") "1 k")
        (field (name "TOLERANCE") "±10%")
        (field (name "PART NUMBER") "3296W-1-102LF")
        (field (name "POWER") "0,5 W")
      )
      (libsource (lib "") (part "Resistor-ADJ_1"))
    )
    (comp (ref "R19")
      (value "10 k")
      (footprint "3296W")
      (fields
        (field (name "VALUESCH") "10 k")
        (field (name "TOLERANCE") "±10%")
        (field (name "PART NUMBER") "3296W-1-103LF")
        (field (name "POWER") "0,5 W")
      )
      (libsource (lib "") (part "Resistor-ADJ_1"))
    )
    (comp (ref "R20")
      (value "100 k")
      (footprint "3296W")
      (fields
        (field (name "VALUESCH") "100 k")
        (field (name "TOLERANCE") "±10%")
        (field (name "PART NUMBER") "3296W-1-104LF")
        (field (name "POWER") "0,5 W")
      )
      (libsource (lib "") (part "Resistor-ADJ_1"))
    )
    (comp (ref "R21")
      (value "1 M")
      (footprint "3296W")
      (fields
        (field (name "VALUESCH") "1 M")
        (field (name "TOLERANCE") "±10%")
        (field (name "PART NUMBER") "3296W-1-105LF")
        (field (name "POWER") "0,5 W")
      )
      (libsource (lib "") (part "Resistor-ADJ_1"))
    )
    (comp (ref "R22")
      (value "0")
      (footprint "R-0805")
      (fields
        (field (name "VALUESCH") "0")
        (field (name "CASE") "0805")
        (field (name "TOLERANCE") "Jumper")
        (field (name "PART NUMBER") "CRCW08050000Z0EA")
        (field (name "POWER") "0,125 W")
        (field (name "MANUFACTURER") "Vishay Dale")
      )
      (libsource (lib "") (part "Resistor_1"))
    )
    (comp (ref "R23")
      (value "0")
      (footprint "R-0805")
      (fields
        (field (name "VALUESCH") "0")
        (field (name "CASE") "0805")
        (field (name "TOLERANCE") "Jumper")
        (field (name "PART NUMBER") "CRCW08050000Z0EA")
        (field (name "POWER") "0,125 W")
        (field (name "MANUFACTURER") "Vishay Dale")
      )
      (libsource (lib "") (part "Resistor_1"))
    )
    (comp (ref "R24")
      (value "10 k")
      (footprint "R-1206")
      (fields
        (field (name "VALUESCH") "10 k")
        (field (name "CASE") "1206")
        (field (name "TOLERANCE") "±1%")
        (field (name "PART NUMBER") "CRCW120610K0FKEA")
        (field (name "POWER") "0,25 W")
        (field (name "MANUFACTURER") "Vishay Dale")
      )
      (libsource (lib "GOST") (part "Resistor"))
    )
    (comp (ref "R25")
      (value "1 k")
      (footprint "R-1206")
      (fields
        (field (name "VALUESCH") "1 k")
        (field (name "CASE") "1206")
        (field (name "TOLERANCE") "±1%")
        (field (name "PART NUMBER") "CRCW12061K00FKEA")
        (field (name "POWER") "0,25 W")
        (field (name "MANUFACTURER") "Vishay Dale")
      )
      (libsource (lib "") (part "Resistor_1"))
    )
    (comp (ref "R26")
      (value "10 k")
      (footprint "3296W")
      (fields
        (field (name "VALUESCH") "10 k")
        (field (name "TOLERANCE") "±10%")
        (field (name "PART NUMBER") "3296W-1-103LF")
        (field (name "POWER") "0,5 W")
        (field (name "MANUFACTURER") "Bourns Inc.")
      )
      (libsource (lib "") (part "Resistor-ADJ_1"))
    )
    (comp (ref "R27")
      (value "22 k")
      (footprint "R-1206")
      (fields
        (field (name "VALUESCH") "22 k")
        (field (name "CASE") "1206")
        (field (name "TOLERANCE") "±1%")
        (field (name "PART NUMBER") "CRCW120622K0FKEA")
        (field (name "POWER") "0,25 W")
        (field (name "MANUFACTURER") "Vishay Dale")
      )
      (libsource (lib "") (part "Resistor_1"))
    )
    (comp (ref "R28")
      (value "0")
      (footprint "R-0805")
      (fields
        (field (name "VALUESCH") "0")
        (field (name "CASE") "0805")
        (field (name "TOLERANCE") "Jumper")
        (field (name "PART NUMBER") "CRCW08050000Z0EA")
        (field (name "POWER") "0,125 W")
        (field (name "MANUFACTURER") "Vishay Dale")
      )
      (libsource (lib "") (part "Resistor_1"))
    )
    (comp (ref "R29")
      (value "2,2 k")
      (footprint "R-1206")
      (fields
        (field (name "VALUESCH") "2,2 k")
        (field (name "CASE") "1206")
        (field (name "TOLERANCE") "±1%")
        (field (name "PART NUMBER") "CRCW12062K20FKEA")
        (field (name "POWER") "0,25 W")
        (field (name "MANUFACTURER") "Vishay Dale")
      )
      (libsource (lib "") (part "Resistor_2"))
    )
    (comp (ref "R30")
      (value "0")
      (footprint "R-0805")
      (fields
        (field (name "VALUESCH") "0")
        (field (name "CASE") "0805")
        (field (name "TOLERANCE") "Jumper")
        (field (name "PART NUMBER") "CRCW08050000Z0EA")
        (field (name "POWER") "0,125 W")
        (field (name "MANUFACTURER") "Vishay Dale")
      )
      (libsource (lib "") (part "Resistor_3"))
    )
    (comp (ref "R31")
      (value "0")
      (footprint "R-0805")
      (fields
        (field (name "VALUESCH") "0")
        (field (name "CASE") "0805")
        (field (name "TOLERANCE") "Jumper")
        (field (name "PART NUMBER") "CRCW08050000Z0EA")
        (field (name "POWER") "0,125 W")
        (field (name "MANUFACTURER") "Vishay Dale")
      )
      (libsource (lib "") (part "Resistor_2"))
    )
    (comp (ref "R32")
      (value "0")
      (footprint "R-0805")
      (fields
        (field (name "VALUESCH") "0")
        (field (name "CASE") "0805")
        (field (name "TOLERANCE") "Jumper")
        (field (name "PART NUMBER") "CRCW08050000Z0EA")
        (field (name "POWER") "0,125 W")
        (field (name "MANUFACTURER") "Vishay Dale")
      )
      (libsource (lib "") (part "Resistor_2"))
    )
    (comp (ref "R33")
      (value "47")
      (footprint "R-1206")
      (fields
        (field (name "VALUESCH") "47")
        (field (name "CASE") "1206")
        (field (name "TOLERANCE") "±5%")
        (field (name "PART NUMBER") "CRCW120647R0JNEA")
        (field (name "POWER") "0,25 W")
        (field (name "MANUFACTURER") "Vishay Dale")
      )
      (libsource (lib "GOST") (part "Resistor"))
    )
    (comp (ref "R34")
      (value "1 k")
      (footprint "R-1206")
      (fields
        (field (name "VALUESCH") "1 k")
        (field (name "TOLERANCE") "±5%")
        (field (name "PART NUMBER") "CRCW12061K00JNEA")
        (field (name "POWER") "0,25 W")
      )
      (libsource (lib "") (part "Resistor_1"))
    )
    (comp (ref "R35")
      (value "1 k")
      (footprint "R-1206")
      (fields
        (field (name "VALUESCH") "1 k")
        (field (name "TOLERANCE") "±5%")
        (field (name "PART NUMBER") "CRCW12061K00JNEA")
        (field (name "POWER") "0,25 W")
      )
      (libsource (lib "") (part "Resistor_1"))
    )
    (comp (ref "R36")
      (value "20 k")
      (footprint "3296W")
      (fields
        (field (name "VALUESCH") "20 k")
        (field (name "TOLERANCE") "±10%")
        (field (name "PART NUMBER") "3296W-1-203LF")
        (field (name "POWER") "0,5 W")
        (field (name "MANUFACTURER") "Bourns Inc.")
      )
      (libsource (lib "") (part "Resistor-ADJ_1"))
    )
    (comp (ref "R37")
      (value "100")
      (footprint "R-1206")
      (fields
        (field (name "VALUESCH") "100")
        (field (name "CASE") "1206")
        (field (name "TOLERANCE") "±5%")
        (field (name "PART NUMBER") "CRCW1206100RJNEA")
        (field (name "POWER") "0,25 W")
        (field (name "MANUFACTURER") "Vishay Dale")
      )
      (libsource (lib "") (part "Resistor_1"))
    )
    (comp (ref "R38")
      (value "1 k")
      (footprint "R-1206")
      (fields
        (field (name "VALUESCH") "1 k")
        (field (name "TOLERANCE") "±5%")
        (field (name "PART NUMBER") "CRCW12061K00JNEA")
        (field (name "POWER") "0,25 W")
      )
      (libsource (lib "") (part "Resistor_1"))
    )
    (comp (ref "R39")
      (value "1 k")
      (footprint "R-1206")
      (fields
        (field (name "VALUESCH") "1 k")
        (field (name "TOLERANCE") "±5%")
        (field (name "PART NUMBER") "CRCW12061K00JNEA")
        (field (name "POWER") "0,25 W")
      )
      (libsource (lib "") (part "Resistor_1"))
    )
    (comp (ref "R40")
      (value "1 k")
      (footprint "R-0805")
      (fields
        (field (name "VALUESCH") "1 k")
        (field (name "CASE") "0805")
        (field (name "TOLERANCE") "±5%")
        (field (name "PART NUMBER") "CRCW08051K00JNEA")
        (field (name "POWER") "0,125 W")
        (field (name "MANUFACTURER") "Vishay Dale")
      )
      (libsource (lib "") (part "Resistor_2"))
    )
    (comp (ref "R41")
      (value "10 k")
      (footprint "R-0805")
      (fields
        (field (name "VALUESCH") "10 k")
        (field (name "CASE") "0805")
        (field (name "TOLERANCE") "±5%")
        (field (name "PART NUMBER") "CRCW080510K0JNEA")
        (field (name "POWER") "0,125 W")
        (field (name "MANUFACTURER") "Vishay Dale")
      )
      (libsource (lib "") (part "Resistor_1"))
    )
    (comp (ref "R42")
      (value "20 k")
      (footprint "3296W")
      (fields
        (field (name "VALUESCH") "20 k")
        (field (name "TOLERANCE") "±10%")
        (field (name "PART NUMBER") "3296W-1-203LF")
        (field (name "POWER") "0,5 W")
        (field (name "MANUFACTURER") "Bourns Inc.")
      )
      (libsource (lib "") (part "Resistor-ADJ_1"))
    )
    (comp (ref "R43")
      (value "10 M")
      (footprint "R-1206")
      (fields
        (field (name "VALUESCH") "10 M")
        (field (name "CASE") "1206")
        (field (name "TOLERANCE") "±1%")
        (field (name "PART NUMBER") "CRCW120610M0FKEA")
        (field (name "POWER") "0,25 W")
        (field (name "MANUFACTURER") "Vishay Dale")
      )
      (libsource (lib "") (part "Resistor_2"))
    )
    (comp (ref "R44")
      (value "51 k")
      (footprint "R-1206")
      (fields
        (field (name "VALUESCH") "51 k")
        (field (name "CASE") "1206")
        (field (name "TOLERANCE") "±5%")
        (field (name "PART NUMBER") "CRCW120651K0JNEA")
        (field (name "POWER") "0,25 W")
        (field (name "MANUFACTURER") "Vishay Dale")
      )
      (libsource (lib "") (part "Resistor_1"))
    )
    (comp (ref "R45")
      (value "15 k")
      (footprint "R-1206")
      (fields
        (field (name "VALUESCH") "15 k")
        (field (name "CASE") "1206")
        (field (name "TOLERANCE") "±1%")
        (field (name "PART NUMBER") "CRCW120615K0FKEA")
        (field (name "POWER") "0,25 W")
        (field (name "MANUFACTURER") "Vishay Dale")
      )
      (libsource (lib "") (part "Resistor_1"))
    )
    (comp (ref "R46")
      (value "2 k")
      (footprint "3296W")
      (fields
        (field (name "VALUESCH") "2 k")
        (field (name "TOLERANCE") "±10%")
        (field (name "PART NUMBER") "3296W-1-202LF")
        (field (name "POWER") "0,5 W")
        (field (name "MANUFACTURER") "Bourns Inc.")
      )
      (libsource (lib "GOST") (part "Resistor-ADJ"))
    )
    (comp (ref "R47")
      (value "1 M")
      (footprint "R-1206")
      (fields
        (field (name "VALUESCH") "1 M")
        (field (name "CASE") "1206")
        (field (name "TOLERANCE") "±1%")
        (field (name "PART NUMBER") "CRCW12061M00FKEA")
        (field (name "POWER") "0,25 W")
        (field (name "MANUFACTURER") "Vishay Dale")
      )
      (libsource (lib "") (part "Resistor_2"))
    )
    (comp (ref "R48")
      (value "100 k")
      (footprint "R-1206")
      (fields
        (field (name "VALUESCH") "100 k")
        (field (name "TOLERANCE") "±1%")
        (field (name "PART NUMBER") "CRCW1206100KFKEA")
        (field (name "POWER") "0,25 W")
      )
      (libsource (lib "GOST") (part "Resistor"))
    )
    (comp (ref "R49")
      (value "15 k")
      (footprint "R-1206")
      (fields
        (field (name "VALUESCH") "15 k")
        (field (name "CASE") "1206")
        (field (name "TOLERANCE") "±1%")
        (field (name "PART NUMBER") "CRCW120615K0FKEA")
        (field (name "POWER") "0,25 W")
        (field (name "MANUFACTURER") "Vishay Dale")
      )
      (libsource (lib "") (part "Resistor_1"))
    )
    (comp (ref "R50")
      (value "10 k")
      (footprint "R-0805")
      (fields
        (field (name "VALUESCH") "10 k")
        (field (name "CASE") "0805")
        (field (name "TOLERANCE") "±5%")
        (field (name "PART NUMBER") "CRCW080510K0JNEA")
        (field (name "POWER") "0,125 W")
        (field (name "MANUFACTURER") "Vishay Dale")
      )
      (libsource (lib "GOST") (part "Resistor"))
    )
    (comp (ref "R51")
      (value "7,5 k")
      (footprint "R-1206")
      (fields
        (field (name "VALUESCH") "7,5 k")
        (field (name "CASE") "1206")
        (field (name "TOLERANCE") "±5%")
        (field (name "PART NUMBER") "CRCW12067K50JNEA")
        (field (name "POWER") "0,25 W")
        (field (name "MANUFACTURER") "Vishay Dale")
      )
      (libsource (lib "") (part "Resistor_1"))
    )
    (comp (ref "R52")
      (value "1 k")
      (footprint "R-0805")
      (fields
        (field (name "VALUESCH") "1 k")
        (field (name "CASE") "0805")
        (field (name "TOLERANCE") "±5%")
        (field (name "PART NUMBER") "CRCW08051K00JNEA")
        (field (name "POWER") "0,125 W")
        (field (name "MANUFACTURER") "Vishay Dale")
      )
      (libsource (lib "") (part "Resistor_1"))
    )
    (comp (ref "R53")
      (value "5 k")
      (footprint "3296W")
      (fields
        (field (name "VALUESCH") "5 k")
        (field (name "TOLERANCE") "±10%")
        (field (name "PART NUMBER") "3296W-1-502LF")
        (field (name "POWER") "0,5 W")
        (field (name "MANUFACTURER") "Bourns Inc.")
      )
      (libsource (lib "GOST") (part "Resistor-ADJ"))
    )
    (comp (ref "R54")
      (value "10 k")
      (footprint "R-1206")
      (fields
        (field (name "VALUESCH") "10 k")
        (field (name "CASE") "1206")
        (field (name "TOLERANCE") "±1%")
        (field (name "PART NUMBER") "CRCW120610K0FKEA")
        (field (name "POWER") "0,25 W")
        (field (name "MANUFACTURER") "Vishay Dale")
      )
      (libsource (lib "") (part "Resistor_2"))
    )
    (comp (ref "R55")
      (value "1 k")
      (footprint "R-1206")
      (fields
        (field (name "VALUESCH") "1 k")
        (field (name "TOLERANCE") "±5%")
        (field (name "PART NUMBER") "CRCW12061K00JNEA")
        (field (name "POWER") "0,25 W")
      )
      (libsource (lib "") (part "Resistor_1"))
    )
    (comp (ref "R56")
      (value "1 k")
      (footprint "R-1206")
      (fields
        (field (name "VALUESCH") "1 k")
        (field (name "TOLERANCE") "±5%")
        (field (name "PART NUMBER") "CRCW12061K00JNEA")
        (field (name "POWER") "0,25 W")
      )
      (libsource (lib "") (part "Resistor_1"))
    )
    (comp (ref "R57")
      (value "6,8 k")
      (footprint "R-1206")
      (fields
        (field (name "VALUESCH") "6,8 k")
        (field (name "CASE") "1206")
        (field (name "TOLERANCE") "±5%")
        (field (name "PART NUMBER") "CRCW12066K80JNEA")
        (field (name "POWER") "0,25 W")
        (field (name "MANUFACTURER") "Vishay Dale")
      )
      (libsource (lib "") (part "Resistor_2"))
    )
    (comp (ref "R58")
      (value "5 k")
      (footprint "3296W")
      (fields
        (field (name "VALUESCH") "5 k")
        (field (name "TOLERANCE") "±10%")
        (field (name "PART NUMBER") "3296W-1-502LF")
        (field (name "POWER") "0,5 W")
        (field (name "MANUFACTURER") "Bourns Inc.")
      )
      (libsource (lib "GOST") (part "Resistor-ADJ"))
    )
    (comp (ref "R59")
      (value "20 k")
      (footprint "3296W")
      (fields
        (field (name "VALUESCH") "20 k")
        (field (name "TOLERANCE") "±10%")
        (field (name "PART NUMBER") "3296W-1-203LF")
        (field (name "POWER") "0,5 W")
        (field (name "MANUFACTURER") "Bourns Inc.")
      )
      (libsource (lib "") (part "Resistor-ADJ_1"))
    )
    (comp (ref "R60")
      (value "51 k")
      (footprint "R-1206")
      (fields
        (field (name "VALUESCH") "51 k")
        (field (name "CASE") "1206")
        (field (name "TOLERANCE") "±5%")
        (field (name "PART NUMBER") "CRCW120651K0JNEA")
        (field (name "POWER") "0,25 W")
        (field (name "MANUFACTURER") "Vishay Dale")
      )
      (libsource (lib "") (part "Resistor_1"))
    )
    (comp (ref "R61")
      (value "1 k")
      (footprint "R-1206")
      (fields
        (field (name "VALUESCH") "1 k")
        (field (name "CASE") "1206")
        (field (name "TOLERANCE") "±1%")
        (field (name "PART NUMBER") "CRCW12061K00FKEA")
        (field (name "POWER") "0,25 W")
        (field (name "MANUFACTURER") "Vishay Dale")
      )
      (libsource (lib "") (part "Resistor_2"))
    )
    (comp (ref "R62")
      (value "10 k")
      (footprint "3296W")
      (fields
        (field (name "VALUESCH") "10 k")
        (field (name "TOLERANCE") "±10%")
        (field (name "PART NUMBER") "3296W-1-103LF")
        (field (name "POWER") "0,5 W")
        (field (name "MANUFACTURER") "Bourns Inc.")
      )
      (libsource (lib "") (part "Resistor-ADJ_2"))
    )
    (comp (ref "R63")
      (value "2 k")
      (footprint "R-1206")
      (fields
        (field (name "VALUESCH") "2 k")
        (field (name "CASE") "1206")
        (field (name "TOLERANCE") "±5%")
        (field (name "PART NUMBER") "CRCW12062K00JNEA")
        (field (name "POWER") "0,25 W")
        (field (name "MANUFACTURER") "Vishay Dale")
      )
      (libsource (lib "") (part "Resistor_2"))
    )
    (comp (ref "R64")
      (value "1 k")
      (footprint "R-1206")
      (fields
        (field (name "VALUESCH") "1 k")
        (field (name "CASE") "1206")
        (field (name "TOLERANCE") "±5%")
        (field (name "PART NUMBER") "CRCW12061K00JNEA")
        (field (name "POWER") "0,25 W")
        (field (name "MANUFACTURER") "Vishay Dale")
      )
      (libsource (lib "") (part "Resistor_1"))
    )
    (comp (ref "R65")
      (value "10 k")
      (footprint "3296W")
      (fields
        (field (name "VALUESCH") "10 k")
        (field (name "TOLERANCE") "±10%")
        (field (name "PART NUMBER") "3296W-1-253LF")
        (field (name "POWER") "0,5 W")
        (field (name "MANUFACTURER") "Bourns Inc.")
      )
      (libsource (lib "GOST") (part "Resistor-ADJ"))
    )
    (comp (ref "R66")
      (value "100")
      (footprint "R-1206")
      (fields
        (field (name "VALUESCH") "100")
        (field (name "CASE") "1206")
        (field (name "TOLERANCE") "±1%")
        (field (name "PART NUMBER") "CRCW1206100RFKEA")
        (field (name "POWER") "0,25 W")
        (field (name "MANUFACTURER") "Vishay Dale")
      )
      (libsource (lib "GOST") (part "Resistor"))
    )
    (comp (ref "T1")
      (value "1P2S")
      (footprint "TH30/12G")
      (fields (field (name "PART NUMBER") "TH30/12G-1.8VA-2x15V"))
      (libsource (lib "GOST") (part "1P2S"))
    )
    (comp (ref "VD1")
      (value "Brige")
      (footprint "DB-S")
      (fields (field (name "PART NUMBER") "DB107S"))
      (libsource (lib "GOST") (part "Brige"))
    )
    (comp (ref "VD2")
      (value "LL4148")
      (footprint "SOD-80")
      (fields (field (name "MANUFACTURER") "ON Semiconductor"))
      (libsource (lib "GOST") (part "Diode"))
    )
    (comp (ref "VD3")
      (value "LL4148")
      (footprint "SOD-80")
      (fields (field (name "MANUFACTURER") "ON Semiconductor"))
      (libsource (lib "GOST") (part "Diode"))
    )
    (comp (ref "VD4")
      (value "LL4148")
      (footprint "SOD-80")
      (fields (field (name "MANUFACTURER") "ON Semiconductor"))
      (libsource (lib "GOST") (part "Diode"))
    )
    (comp (ref "VD5")
      (value "LL4148")
      (footprint "SOD-80")
      (fields (field (name "MANUFACTURER") "ON Semiconductor"))
      (libsource (lib "GOST") (part "Diode"))
    )
    (comp (ref "VD6")
      (value "LL4148")
      (footprint "SOD-80")
      (fields (field (name "MANUFACTURER") "ON Semiconductor"))
      (libsource (lib "GOST") (part "Diode"))
    )
    (comp (ref "VT1")
      (value "BC848")
      (footprint "SOT-23")
      (fields (field (name "PART NUMBER") "BC847") (field (name "MANUFACTURER") "ON Semiconductor"))
      (libsource (lib "GOST") (part "BJT-NPN"))
    )
    (comp (ref "VT2")
      (value "BC848")
      (footprint "SOT-23")
      (fields (field (name "PART NUMBER") "BC847") (field (name "MANUFACTURER") "ON Semiconductor"))
      (libsource (lib "GOST") (part "BJT-NPN"))
    )
    (comp (ref "VT3")
      (value "JFET-N")
      (footprint "SOT-23")
      (fields (field (name "PART NUMBER") "PMBFJ309") (field (name "MANUFACTURER") "NXP Semiconductors"))
      (libsource (lib "GOST") (part "JFET-N"))
    )
    (comp (ref "VT4")
      (value "JFET-N")
      (footprint "SOT-23")
      (fields (field (name "PART NUMBER") "PMBFJ309") (field (name "MANUFACTURER") "NXP Semiconductors"))
      (libsource (lib "GOST") (part "JFET-N"))
    )
    (comp (ref "XP1")
      (value "Text")
      (footprint "61300311121")
      (fields (field (name "PART NUMBER") "61300311121") (field (name "MANUFACTURER") "Würth Elektronik"))
      (libsource (lib "GOST") (part "Con-3-M"))
    )
    (comp (ref "XP2")
      (value "Text")
      (footprint "61900311121")
      (fields (field (name "PART NUMBER") "61900311121") (field (name "MANUFACTURER") "Würth Elektronik"))
      (libsource (lib "GOST") (part "Con-3-M"))
    )
    (comp (ref "XP3")
      (value "Text")
      (footprint "61300711121")
      (fields (field (name "PART NUMBER") "61300711121") (field (name "MANUFACTURER") "Würth Elektronik"))
      (libsource (lib "GOST") (part "Con-7-M"))
    )
    (comp (ref "XP4")
      (value "Text")
      (footprint "61300511121")
      (fields (field (name "PART NUMBER") "61300511121") (field (name "MANUFACTURER") "Würth Elektronik"))
      (libsource (lib "GOST") (part "Con-5-M"))
    )
    (comp (ref "XP5")
      (value "Text")
      (footprint "61300211121")
      (fields (field (name "PART NUMBER") "61300211121") (field (name "MANUFACTURER") "Würth Elektronik"))
      (libsource (lib "GOST") (part "Con-2-M"))
    )
    (comp (ref "XP6")
      (value "Text")
      (footprint "61300211121")
      (fields (field (name "PART NUMBER") "61300211121") (field (name "MANUFACTURER") "Würth Elektronik"))
      (libsource (lib "GOST") (part "Con-2-M"))
    )
    (comp (ref "XP7")
      (value "Text")
      (footprint "61300211121")
      (fields (field (name "PART NUMBER") "61300211121") (field (name "MANUFACTURER") "Würth Elektronik"))
      (libsource (lib "GOST") (part "Con-2-M"))
    )
    (comp (ref "XP8")
      (value "Text")
      (footprint "61300211121")
      (fields (field (name "PART NUMBER") "61300211121") (field (name "MANUFACTURER") "Würth Elektronik"))
      (libsource (lib "GOST") (part "Con-2-M"))
    )
    (comp (ref "XP9")
      (value "Text")
      (footprint "61300211121")
      (fields (field (name "PART NUMBER") "61300211121") (field (name "MANUFACTURER") "Würth Elektronik"))
      (libsource (lib "GOST") (part "Con-2-M"))
    )
    (comp (ref "XP10")
      (value "Text")
      (footprint "61300211121")
      (fields (field (name "PART NUMBER") "61300211121") (field (name "MANUFACTURER") "Würth Elektronik"))
      (libsource (lib "GOST") (part "Con-2-M"))
    )
    (comp (ref "XP11")
      (value "Text")
      (footprint "61300711121")
      (fields (field (name "PART NUMBER") "61300711121") (field (name "MANUFACTURER") "Würth Elektronik"))
      (libsource (lib "GOST") (part "Con-7-M"))
    )
  )
  (nets
    (net (code "1") (name "+5V") (class "Default")
      (node (ref "C27") (pin "2") (pinfunction "2_2") (pintype "power_in"))
      (node (ref "C30") (pin "2") (pinfunction "2_2") (pintype "power_in"))
      (node (ref "C33") (pin "2") (pinfunction "2_2") (pintype "power_in"))
      (node (ref "DA7") (pin "2") (pinfunction "OUT_2") (pintype "passive"))
    )
    (net (code "2") (name "+12V") (class "Default")
      (node (ref "C16") (pin "1") (pinfunction "1_1") (pintype "power_in"))
      (node (ref "C18") (pin "2") (pinfunction "2_2") (pintype "power_in"))
      (node (ref "C22") (pin "2") (pinfunction "2_2") (pintype "power_in"))
      (node (ref "C23") (pin "2") (pinfunction "2_2") (pintype "power_in"))
      (node (ref "C25") (pin "2") (pinfunction "2_2") (pintype "power_in"))
      (node (ref "C28") (pin "2") (pinfunction "2_2") (pintype "power_in"))
      (node (ref "C31") (pin "2") (pinfunction "2_2") (pintype "power_in"))
      (node (ref "C34") (pin "2") (pinfunction "2_2") (pintype "power_in"))
      (node (ref "DA1") (pin "8") (pinfunction "V+_8") (pintype "passive"))
      (node (ref "DA2") (pin "16") (pinfunction "VDD_16") (pintype "passive"))
      (node (ref "DA3") (pin "8") (pinfunction "V+_8") (pintype "passive"))
      (node (ref "DA4") (pin "2") (pinfunction "OUT_2") (pintype "passive"))
      (node (ref "DA6") (pin "7") (pinfunction "V+_7") (pintype "passive"))
      (node (ref "DA8") (pin "7") (pinfunction "V+_7") (pintype "passive"))
      (node (ref "DA9") (pin "7") (pinfunction "V+_7") (pintype "passive"))
      (node (ref "R1") (pin "1") (pinfunction "1_1") (pintype "passive"))
      (node (ref "R22") (pin "1") (pinfunction "1_1") (pintype "passive"))
      (node (ref "R30") (pin "2") (pinfunction "2_2") (pintype "passive"))
      (node (ref "R36") (pin "2") (pinfunction "2_2") (pintype "passive"))
      (node (ref "R42") (pin "2") (pinfunction "2_2") (pintype "passive"))
      (node (ref "R59") (pin "2") (pinfunction "2_2") (pintype "passive"))
    )
    (net (code "3") (name "-12V") (class "Default")
      (node (ref "C17") (pin "2") (pinfunction "2_2") (pintype "power_in"))
      (node (ref "C19") (pin "2") (pinfunction "2_2") (pintype "power_in"))
      (node (ref "C21") (pin "2") (pinfunction "2_2") (pintype "power_in"))
      (node (ref "C24") (pin "2") (pinfunction "2_2") (pintype "power_in"))
      (node (ref "C26") (pin "2") (pinfunction "2_2") (pintype "power_in"))
      (node (ref "C29") (pin "2") (pinfunction "2_2") (pintype "power_in"))
      (node (ref "C32") (pin "2") (pinfunction "2_2") (pintype "power_in"))
      (node (ref "C35") (pin "1") (pinfunction "1_1") (pintype "power_in"))
      (node (ref "DA1") (pin "4") (pinfunction "V-_4") (pintype "passive"))
      (node (ref "DA2") (pin "7") (pinfunction "VEE_7") (pintype "passive"))
      (node (ref "DA3") (pin "4") (pinfunction "V-_4") (pintype "passive"))
      (node (ref "DA5") (pin "2") (pinfunction "OUT_2") (pintype "passive"))
      (node (ref "DA6") (pin "4") (pinfunction "V-_4") (pintype "passive"))
      (node (ref "DA8") (pin "4") (pinfunction "V-_4") (pintype "passive"))
      (node (ref "DA9") (pin "4") (pinfunction "V-_4") (pintype "passive"))
      (node (ref "R23") (pin "1") (pinfunction "1_1") (pintype "passive"))
      (node (ref "R28") (pin "1") (pinfunction "1_1") (pintype "passive"))
    )
    (net (code "4") (name "/A") (class "Default")
      (node (ref "DA2") (pin "11") (pinfunction "A_11") (pintype "passive"))
    )
    (net (code "5") (name "/B") (class "Default")
      (node (ref "DA2") (pin "10") (pinfunction "B_10") (pintype "passive"))
    )
    (net (code "6") (name "/C") (class "Default")
      (node (ref "DA2") (pin "9") (pinfunction "C_9") (pintype "passive"))
    )
    (net (code "7") (name "/GND_5V") (class "Default")
      (node (ref "C27") (pin "1") (pinfunction "1_1") (pintype "power_in"))
      (node (ref "C30") (pin "1") (pinfunction "1_1") (pintype "power_in"))
      (node (ref "C33") (pin "1") (pinfunction "1_1") (pintype "power_in"))
      (node (ref "DA7") (pin "3") (pinfunction "GND_3") (pintype "passive"))
      (node (ref "R28") (pin "2") (pinfunction "2_2") (pintype "passive"))
      (node (ref "R32") (pin "2") (pinfunction "2_2") (pintype "passive"))
    )
    (net (code "8") (name "/INH") (class "Default")
      (node (ref "DA2") (pin "6") (pinfunction "INH_6") (pintype "passive"))
    )
    (net (code "9") (name "/LEVEL") (class "Default")
      (node (ref "R40") (pin "2") (pinfunction "2_2") (pintype "passive"))
      (node (ref "R41") (pin "1") (pinfunction "1_1") (pintype "passive"))
    )
    (net (code "10") (name "/MAX_LEV") (class "Default")
      (node (ref "R50") (pin "1") (pinfunction "1_1") (pintype "passive"))
      (node (ref "R52") (pin "2") (pinfunction "2_2") (pintype "passive"))
    )
    (net (code "11") (name "/MIN_LEV") (class "Default")
      (node (ref "C40") (pin "1") (pinfunction "1_1") (pintype "power_in"))
      (node (ref "C42") (pin "1") (pinfunction "1_1") (pintype "power_in"))
      (node (ref "KT4") (pin "1") (pinfunction "1_1") (pintype "passive"))
      (node (ref "R46") (pin "2") (pinfunction "2_2") (pintype "passive"))
      (node (ref "R46") (pin "3") (pinfunction "3_3") (pintype "passive"))
      (node (ref "R51") (pin "1") (pinfunction "1_1") (pintype "passive"))
      (node (ref "XP7") (pin "1") (pintype "passive"))
    )
    (net (code "12") (name "/SYNCH") (class "Default")
      (node (ref "R24") (pin "1") (pinfunction "1_1") (pintype "passive"))
      (node (ref "R25") (pin "2") (pinfunction "2_2") (pintype "passive"))
    )
    (net (code "13") (name "/TRIANGLE") (class "Default")
      (node (ref "R3") (pin "1") (pinfunction "1_1") (pintype "passive"))
    )
    (net (code "14") (name "GND") (class "Default")
      (node (ref "C1") (pin "1") (pinfunction "1_1") (pintype "power_in"))
      (node (ref "C10") (pin "2") (pinfunction "2_2") (pintype "power_in"))
      (node (ref "C11") (pin "1") (pinfunction "1_1") (pintype "power_in"))
      (node (ref "C12") (pin "2") (pinfunction "2_2") (pintype "power_in"))
      (node (ref "C13") (pin "1") (pinfunction "1_1") (pintype "power_in"))
      (node (ref "C14") (pin "1") (pinfunction "1_1") (pintype "power_in"))
      (node (ref "C16") (pin "2") (pinfunction "2_2") (pintype "power_in"))
      (node (ref "C17") (pin "1") (pinfunction "1_1") (pintype "power_in"))
      (node (ref "C18") (pin "1") (pinfunction "1_1") (pintype "power_in"))
      (node (ref "C19") (pin "1") (pinfunction "1_1") (pintype "power_in"))
      (node (ref "C20") (pin "1") (pinfunction "1_1") (pintype "power_in"))
      (node (ref "C21") (pin "1") (pinfunction "1_1") (pintype "power_in"))
      (node (ref "C22") (pin "1") (pinfunction "1_1") (pintype "power_in"))
      (node (ref "C23") (pin "1") (pinfunction "1_1") (pintype "power_in"))
      (node (ref "C24") (pin "1") (pinfunction "1_1") (pintype "power_in"))
      (node (ref "C25") (pin "1") (pinfunction "1_1") (pintype "power_in"))
      (node (ref "C26") (pin "1") (pinfunction "1_1") (pintype "power_in"))
      (node (ref "C28") (pin "1") (pinfunction "1_1") (pintype "power_in"))
      (node (ref "C29") (pin "1") (pinfunction "1_1") (pintype "power_in"))
      (node (ref "C3") (pin "1") (pinfunction "1_1") (pintype "power_in"))
      (node (ref "C31") (pin "1") (pinfunction "1_1") (pintype "power_in"))
      (node (ref "C32") (pin "1") (pinfunction "1_1") (pintype "power_in"))
      (node (ref "C34") (pin "1") (pinfunction "1_1") (pintype "power_in"))
      (node (ref "C35") (pin "2") (pinfunction "2_2") (pintype "power_in"))
      (node (ref "C40") (pin "2") (pinfunction "2_2") (pintype "power_in"))
      (node (ref "C42") (pin "2") (pinfunction "2_2") (pintype "power_in"))
      (node (ref "C44") (pin "2") (pinfunction "2_2") (pintype "power_in"))
      (node (ref "C45") (pin "2") (pinfunction "2_2") (pintype "power_in"))
      (node (ref "C7") (pin "2") (pinfunction "2_2") (pintype "power_in"))
      (node (ref "C8") (pin "1") (pinfunction "1_1") (pintype "power_in"))
      (node (ref "C9") (pin "1") (pinfunction "1_1") (pintype "power_in"))
      (node (ref "DA1") (pin "3") (pinfunction "+IN_3") (pintype "passive"))
      (node (ref "DA1") (pin "5") (pinfunction "+IN_5") (pintype "passive"))
      (node (ref "DA2") (pin "8") (pinfunction "VSS/GND_8") (pintype "passive"))
      (node (ref "DA4") (pin "3") (pinfunction "GND_3") (pintype "passive"))
      (node (ref "DA5") (pin "1") (pinfunction "GND_1") (pintype "passive"))
      (node (ref "DA8") (pin "3") (pinfunction "+IN_3") (pintype "passive"))
      (node (ref "DA9") (pin "3") (pinfunction "+IN_3") (pintype "passive"))
      (node (ref "R2") (pin "1") (pinfunction "1_1") (pintype "passive"))
      (node (ref "R25") (pin "1") (pinfunction "1_1") (pintype "passive"))
      (node (ref "R26") (pin "3") (pinfunction "3_3") (pintype "passive"))
      (node (ref "R29") (pin "1") (pinfunction "1_1") (pintype "passive"))
      (node (ref "R31") (pin "1") (pinfunction "1_1") (pintype "passive"))
      (node (ref "R32") (pin "1") (pinfunction "1_1") (pintype "passive"))
      (node (ref "R40") (pin "1") (pinfunction "1_1") (pintype "passive"))
      (node (ref "R46") (pin "1") (pinfunction "1_1") (pintype "passive"))
      (node (ref "R52") (pin "1") (pinfunction "1_1") (pintype "passive"))
      (node (ref "R62") (pin "1") (pinfunction "1_1") (pintype "passive"))
      (node (ref "R8") (pin "3") (pinfunction "3_3") (pintype "passive"))
      (node (ref "T1") (pin "4") (pinfunction "4_4") (pintype "passive"))
      (node (ref "T1") (pin "5") (pinfunction "5_5") (pintype "passive"))
      (node (ref "VT1") (pin "2") (pinfunction "2_2") (pintype "passive"))
      (node (ref "XP1") (pin "2") (pintype "passive"))
      (node (ref "XP10") (pin "2") (pintype "passive"))
      (node (ref "XP7") (pin "2") (pintype "passive"))
      (node (ref "XP8") (pin "2") (pintype "passive"))
      (node (ref "XP9") (pin "2") (pintype "passive"))
    )
    (net (code "15") (name "Net-(C1-Pad2)") (class "Default")
      (node (ref "C1") (pin "2") (pinfunction "2_2") (pintype "power_in"))
      (node (ref "KT1") (pin "1") (pinfunction "1_1") (pintype "passive"))
      (node (ref "R3") (pin "2") (pinfunction "2_2") (pintype "passive"))
      (node (ref "R4") (pin "2") (pinfunction "2_2") (pintype "passive"))
    )
    (net (code "16") (name "Net-(C2-Pad1)") (class "Default")
      (node (ref "C2") (pin "1") (pinfunction "1_1") (pintype "power_in"))
      (node (ref "R4") (pin "1") (pinfunction "1_1") (pintype "passive"))
      (node (ref "R5") (pin "1") (pinfunction "1_1") (pintype "passive"))
      (node (ref "XP1") (pin "3") (pintype "passive"))
    )
    (net (code "17") (name "Net-(C6-Pad1)") (class "Default")
      (node (ref "C6") (pin "1") (pinfunction "1_1") (pintype "power_in"))
      (node (ref "R8") (pin "2") (pinfunction "2_2") (pintype "passive"))
    )
    (net (code "18") (name "Net-(C20-Pad2)") (class "Default")
      (node (ref "C20") (pin "2") (pinfunction "2_2") (pintype "power_in"))
      (node (ref "R33") (pin "2") (pinfunction "2_2") (pintype "passive"))
    )
    (net (code "19") (name "Net-(C36-Pad1)") (class "Default")
      (node (ref "C36") (pin "1") (pinfunction "1_1") (pintype "power_in"))
      (node (ref "C38") (pin "1") (pinfunction "1_1") (pintype "power_in"))
      (node (ref "C39") (pin "1") (pinfunction "1_1") (pintype "power_in"))
      (node (ref "C41") (pin "2") (pinfunction "2_2") (pintype "power_in"))
      (node (ref "C43") (pin "2") (pinfunction "2_2") (pintype "power_in"))
      (node (ref "C46") (pin "2") (pinfunction "2_2") (pintype "power_in"))
      (node (ref "C47") (pin "2") (pinfunction "2_2") (pintype "power_in"))
      (node (ref "C6") (pin "2") (pinfunction "2_2") (pintype "power_in"))
      (node (ref "R37") (pin "2") (pinfunction "2_2") (pintype "passive"))
      (node (ref "R43") (pin "1") (pinfunction "1_1") (pintype "passive"))
      (node (ref "R47") (pin "1") (pinfunction "1_1") (pintype "passive"))
      (node (ref "R48") (pin "2") (pinfunction "2_2") (pintype "passive"))
      (node (ref "R54") (pin "1") (pinfunction "1_1") (pintype "passive"))
      (node (ref "R61") (pin "1") (pinfunction "1_1") (pintype "passive"))
      (node (ref "R66") (pin "2") (pinfunction "2_2") (pintype "passive"))
      (node (ref "XP6") (pin "2") (pintype "passive"))
    )
    (net (code "20") (name "Net-(C36-Pad2)") (class "Default")
      (node (ref "C36") (pin "2") (pinfunction "2_2") (pintype "power_in"))
      (node (ref "R43") (pin "2") (pinfunction "2_2") (pintype "passive"))
      (node (ref "XP11") (pin "1") (pintype "passive"))
    )
    (net (code "21") (name "Net-(C38-Pad2)") (class "Default")
      (node (ref "C38") (pin "2") (pinfunction "2_2") (pintype "power_in"))
      (node (ref "R47") (pin "2") (pinfunction "2_2") (pintype "passive"))
      (node (ref "XP11") (pin "2") (pintype "passive"))
    )
    (net (code "22") (name "Net-(C39-Pad2)") (class "Default")
      (node (ref "C39") (pin "2") (pinfunction "2_2") (pintype "power_in"))
      (node (ref "R62") (pin "2") (pinfunction "2_2") (pintype "passive"))
    )
    (net (code "23") (name "Net-(C41-Pad1)") (class "Default")
      (node (ref "C41") (pin "1") (pinfunction "1_1") (pintype "power_in"))
      (node (ref "R48") (pin "1") (pinfunction "1_1") (pintype "passive"))
      (node (ref "XP11") (pin "3") (pintype "passive"))
    )
    (net (code "24") (name "Net-(C43-Pad1)") (class "Default")
      (node (ref "C43") (pin "1") (pinfunction "1_1") (pintype "power_in"))
      (node (ref "R54") (pin "2") (pinfunction "2_2") (pintype "passive"))
      (node (ref "XP11") (pin "4") (pintype "passive"))
    )
    (net (code "25") (name "Net-(C44-Pad1)") (class "Default")
      (node (ref "C44") (pin "1") (pinfunction "1_1") (pintype "power_in"))
      (node (ref "C45") (pin "1") (pinfunction "1_1") (pintype "power_in"))
      (node (ref "R57") (pin "1") (pinfunction "1_1") (pintype "passive"))
      (node (ref "R58") (pin "1") (pinfunction "1_1") (pintype "passive"))
    )
    (net (code "26") (name "Net-(C46-Pad1)") (class "Default")
      (node (ref "C46") (pin "1") (pinfunction "1_1") (pintype "power_in"))
      (node (ref "R61") (pin "2") (pinfunction "2_2") (pintype "passive"))
      (node (ref "XP11") (pin "5") (pintype "passive"))
    )
    (net (code "27") (name "Net-(C47-Pad1)") (class "Default")
      (node (ref "C47") (pin "1") (pinfunction "1_1") (pintype "power_in"))
      (node (ref "R66") (pin "1") (pinfunction "1_1") (pintype "passive"))
      (node (ref "XP11") (pin "6") (pintype "passive"))
    )
    (net (code "28") (name "Net-(DA1A--IN)") (class "Default")
      (node (ref "DA1") (pin "2") (pinfunction "-IN_2") (pintype "passive"))
      (node (ref "R10") (pin "1") (pinfunction "1_1") (pintype "passive"))
      (node (ref "R7") (pin "2") (pinfunction "2_2") (pintype "passive"))
    )
    (net (code "29") (name "Net-(DA1A-OUT)") (class "Default")
      (node (ref "DA1") (pin "1") (pinfunction "OUT_1") (pintype "passive"))
      (node (ref "KT2") (pin "1") (pinfunction "1_1") (pintype "passive"))
      (node (ref "R6") (pin "2") (pinfunction "2_2") (pintype "passive"))
      (node (ref "R7") (pin "1") (pinfunction "1_1") (pintype "passive"))
      (node (ref "R8") (pin "1") (pinfunction "1_1") (pintype "passive"))
    )
    (net (code "30") (name "Net-(DA1B--IN)") (class "Default")
      (node (ref "DA1") (pin "6") (pinfunction "-IN_6") (pintype "passive"))
      (node (ref "R11") (pin "2") (pinfunction "2_2") (pintype "passive"))
      (node (ref "R12") (pin "1") (pinfunction "1_1") (pintype "passive"))
    )
    (net (code "31") (name "Net-(DA1B-OUT)") (class "Default")
      (node (ref "DA1") (pin "7") (pinfunction "OUT_7") (pintype "passive"))
      (node (ref "KT3") (pin "1") (pinfunction "1_1") (pintype "passive"))
      (node (ref "R12") (pin "2") (pinfunction "2_2") (pintype "passive"))
      (node (ref "VD3") (pin "1") (pinfunction "1_1") (pintype "passive"))
      (node (ref "VD4") (pin "2") (pinfunction "2_2") (pintype "passive"))
    )
    (net (code "32") (name "Net-(DA2-CH0)") (class "Default")
      (node (ref "DA2") (pin "13") (pinfunction "CH0_13") (pintype "passive"))
      (node (ref "XP3") (pin "1") (pintype "passive"))
    )
    (net (code "33") (name "Net-(DA2-CH1)") (class "Default")
      (node (ref "DA2") (pin "14") (pinfunction "CH1_14") (pintype "passive"))
      (node (ref "XP3") (pin "2") (pintype "passive"))
    )
    (net (code "34") (name "Net-(DA2-CH2)") (class "Default")
      (node (ref "DA2") (pin "15") (pinfunction "CH2_15") (pintype "passive"))
      (node (ref "XP3") (pin "3") (pintype "passive"))
    )
    (net (code "35") (name "Net-(DA2-CH3)") (class "Default")
      (node (ref "DA2") (pin "12") (pinfunction "CH3_12") (pintype "passive"))
      (node (ref "XP3") (pin "4") (pintype "passive"))
    )
    (net (code "36") (name "Net-(DA2-CH4)") (class "Default")
      (node (ref "DA2") (pin "1") (pinfunction "CH4_1") (pintype "passive"))
      (node (ref "XP3") (pin "5") (pintype "passive"))
    )
    (net (code "37") (name "Net-(DA2-CH5)") (class "Default")
      (node (ref "DA2") (pin "5") (pinfunction "CH5_5") (pintype "passive"))
      (node (ref "XP3") (pin "6") (pintype "passive"))
    )
    (net (code "38") (name "Net-(DA2-COM)") (class "Default")
      (node (ref "DA2") (pin "3") (pinfunction "COM_3") (pintype "passive"))
      (node (ref "XP3") (pin "7") (pintype "passive"))
    )
    (net (code "39") (name "Net-(DA3A-+IN)") (class "Default")
      (node (ref "C3") (pin "2") (pinfunction "2_2") (pintype "power_in"))
      (node (ref "C4") (pin "1") (pinfunction "1_1") (pintype "power_in"))
      (node (ref "DA3") (pin "3") (pinfunction "+IN_3") (pintype "passive"))
      (node (ref "R5") (pin "2") (pinfunction "2_2") (pintype "passive"))
      (node (ref "R9") (pin "1") (pinfunction "1_1") (pintype "passive"))
    )
    (net (code "40") (name "Net-(DA3A--IN)") (class "Default")
      (node (ref "C2") (pin "2") (pinfunction "2_2") (pintype "power_in"))
      (node (ref "C5") (pin "2") (pinfunction "2_2") (pintype "power_in"))
      (node (ref "DA3") (pin "2") (pinfunction "-IN_2") (pintype "passive"))
      (node (ref "R6") (pin "1") (pinfunction "1_1") (pintype "passive"))
    )
    (net (code "41") (name "Net-(DA3A-OUT)") (class "Default")
      (node (ref "C4") (pin "2") (pinfunction "2_2") (pintype "power_in"))
      (node (ref "C5") (pin "1") (pinfunction "1_1") (pintype "power_in"))
      (node (ref "DA3") (pin "1") (pinfunction "OUT_1") (pintype "passive"))
      (node (ref "R11") (pin "1") (pinfunction "1_1") (pintype "passive"))
      (node (ref "R17") (pin "1") (pinfunction "1_1") (pintype "passive"))
      (node (ref "R9") (pin "2") (pinfunction "2_2") (pintype "passive"))
      (node (ref "VD2") (pin "2") (pinfunction "2_2") (pintype "passive"))
      (node (ref "XP4") (pin "5") (pintype "passive"))
    )
    (net (code "42") (name "Net-(DA3B-+IN)") (class "Default")
      (node (ref "DA3") (pin "5") (pinfunction "+IN_5") (pintype "passive"))
      (node (ref "R26") (pin "2") (pinfunction "2_2") (pintype "passive"))
    )
    (net (code "43") (name "Net-(DA3B--IN)") (class "Default")
      (node (ref "C15") (pin "1") (pinfunction "1_1") (pintype "power_in"))
      (node (ref "DA3") (pin "6") (pinfunction "-IN_6") (pintype "passive"))
      (node (ref "R17") (pin "2") (pinfunction "2_2") (pintype "passive"))
      (node (ref "R18") (pin "2") (pinfunction "2_2") (pintype "passive"))
      (node (ref "R18") (pin "3") (pinfunction "3_3") (pintype "passive"))
      (node (ref "R19") (pin "2") (pinfunction "2_2") (pintype "passive"))
      (node (ref "R19") (pin "3") (pinfunction "3_3") (pintype "passive"))
      (node (ref "R20") (pin "2") (pinfunction "2_2") (pintype "passive"))
      (node (ref "R20") (pin "3") (pinfunction "3_3") (pintype "passive"))
      (node (ref "R21") (pin "2") (pinfunction "2_2") (pintype "passive"))
      (node (ref "R21") (pin "3") (pinfunction "3_3") (pintype "passive"))
    )
    (net (code "44") (name "Net-(DA3B-OUT)") (class "Default")
      (node (ref "C15") (pin "2") (pinfunction "2_2") (pintype "power_in"))
      (node (ref "DA3") (pin "7") (pinfunction "OUT_7") (pintype "passive"))
      (node (ref "R10") (pin "2") (pinfunction "2_2") (pintype "passive"))
      (node (ref "R27") (pin "1") (pinfunction "1_1") (pintype "passive"))
      (node (ref "XP5") (pin "1") (pintype "passive"))
    )
    (net (code "45") (name "Net-(DA4-IN)") (class "Default")
      (node (ref "C10") (pin "1") (pinfunction "1_1") (pintype "power_in"))
      (node (ref "C12") (pin "1") (pinfunction "1_1") (pintype "power_in"))
      (node (ref "C13") (pin "2") (pinfunction "2_2") (pintype "power_in"))
      (node (ref "C7") (pin "1") (pinfunction "1_1") (pintype "power_in"))
      (node (ref "DA4") (pin "1") (pinfunction "IN_1") (pintype "passive"))
      (node (ref "F1") (pin "2") (pinfunction "2_2") (pintype "passive"))
    )
    (net (code "46") (name "Net-(DA5-IN)") (class "Default")
      (node (ref "C11") (pin "2") (pinfunction "2_2") (pintype "power_in"))
      (node (ref "C14") (pin "2") (pinfunction "2_2") (pintype "power_in"))
      (node (ref "C8") (pin "2") (pinfunction "2_2") (pintype "power_in"))
      (node (ref "C9") (pin "2") (pinfunction "2_2") (pintype "power_in"))
      (node (ref "DA5") (pin "3") (pinfunction "IN_3") (pintype "passive"))
      (node (ref "F2") (pin "2") (pinfunction "2_2") (pintype "passive"))
    )
    (net (code "47") (name "Net-(DA6-+IN)") (class "Default")
      (node (ref "DA6") (pin "3") (pinfunction "+IN_3") (pintype "passive"))
      (node (ref "R27") (pin "2") (pinfunction "2_2") (pintype "passive"))
      (node (ref "R29") (pin "2") (pinfunction "2_2") (pintype "passive"))
      (node (ref "XP5") (pin "2") (pintype "passive"))
    )
    (net (code "48") (name "Net-(DA6--IN)") (class "Default")
      (node (ref "DA6") (pin "2") (pinfunction "-IN_2") (pintype "passive"))
      (node (ref "DA6") (pin "6") (pinfunction "OUT_6") (pintype "passive"))
      (node (ref "R33") (pin "1") (pinfunction "1_1") (pintype "passive"))
      (node (ref "XP6") (pin "1") (pintype "passive"))
    )
    (net (code "49") (name "Net-(DA6-ON1)") (class "Default")
      (node (ref "DA6") (pin "1") (pinfunction "ON1_1") (pintype "passive"))
      (node (ref "R34") (pin "1") (pinfunction "1_1") (pintype "passive"))
    )
    (net (code "50") (name "Net-(DA6-ON2)") (class "Default")
      (node (ref "DA6") (pin "5") (pinfunction "ON2_5") (pintype "passive"))
      (node (ref "R35") (pin "1") (pinfunction "1_1") (pintype "passive"))
    )
    (net (code "51") (name "Net-(DA7-IN)") (class "Default")
      (node (ref "DA7") (pin "1") (pinfunction "IN_1") (pintype "passive"))
      (node (ref "R30") (pin "1") (pinfunction "1_1") (pintype "passive"))
      (node (ref "R31") (pin "2") (pinfunction "2_2") (pintype "passive"))
    )
    (net (code "52") (name "Net-(DA8--IN)") (class "Default")
      (node (ref "DA8") (pin "2") (pinfunction "-IN_2") (pintype "passive"))
      (node (ref "R37") (pin "1") (pinfunction "1_1") (pintype "passive"))
      (node (ref "VT2") (pin "2") (pinfunction "2_2") (pintype "passive"))
    )
    (net (code "53") (name "Net-(DA8-ON1)") (class "Default")
      (node (ref "C37") (pin "2") (pinfunction "2_2") (pintype "power_in"))
      (node (ref "DA8") (pin "1") (pinfunction "ON1_1") (pintype "passive"))
      (node (ref "R38") (pin "1") (pinfunction "1_1") (pintype "passive"))
    )
    (net (code "54") (name "Net-(DA8-ON2)") (class "Default")
      (node (ref "C37") (pin "1") (pinfunction "1_1") (pintype "power_in"))
      (node (ref "DA8") (pin "5") (pinfunction "ON2_5") (pintype "passive"))
      (node (ref "R39") (pin "1") (pinfunction "1_1") (pintype "passive"))
    )
    (net (code "55") (name "Net-(DA8-OUT)") (class "Default")
      (node (ref "DA8") (pin "6") (pinfunction "OUT_6") (pintype "passive"))
      (node (ref "R41") (pin "2") (pinfunction "2_2") (pintype "passive"))
      (node (ref "R44") (pin "1") (pinfunction "1_1") (pintype "passive"))
      (node (ref "R45") (pin "1") (pinfunction "1_1") (pintype "passive"))
      (node (ref "R64") (pin "1") (pinfunction "1_1") (pintype "passive"))
      (node (ref "VD5") (pin "1") (pinfunction "1_1") (pintype "passive"))
      (node (ref "VT3") (pin "2") (pinfunction "D_2") (pintype "passive"))
      (node (ref "XP11") (pin "7") (pintype "passive"))
    )
    (net (code "56") (name "Net-(DA9--IN)") (class "Default")
      (node (ref "DA9") (pin "2") (pinfunction "-IN_2") (pintype "passive"))
      (node (ref "R45") (pin "2") (pinfunction "2_2") (pintype "passive"))
      (node (ref "R49") (pin "1") (pinfunction "1_1") (pintype "passive"))
    )
    (net (code "57") (name "Net-(DA9-ON1)") (class "Default")
      (node (ref "DA9") (pin "1") (pinfunction "ON1_1") (pintype "passive"))
      (node (ref "R55") (pin "1") (pinfunction "1_1") (pintype "passive"))
    )
    (net (code "58") (name "Net-(DA9-ON2)") (class "Default")
      (node (ref "DA9") (pin "5") (pinfunction "ON2_5") (pintype "passive"))
      (node (ref "R56") (pin "1") (pinfunction "1_1") (pintype "passive"))
    )
    (net (code "59") (name "Net-(DA9-OUT)") (class "Default")
      (node (ref "DA9") (pin "6") (pinfunction "OUT_6") (pintype "passive"))
      (node (ref "R49") (pin "2") (pinfunction "2_2") (pintype "passive"))
      (node (ref "R60") (pin "2") (pinfunction "2_2") (pintype "passive"))
      (node (ref "R62") (pin "3") (pinfunction "3_3") (pintype "passive"))
      (node (ref "VD6") (pin "1") (pinfunction "1_1") (pintype "passive"))
      (node (ref "VT4") (pin "2") (pinfunction "D_2") (pintype "passive"))
    )
    (net (code "60") (name "Net-(F1-Pad1)") (class "Default")
      (node (ref "F1") (pin "1") (pinfunction "1_1") (pintype "passive"))
      (node (ref "VD1") (pin "3") (pinfunction "3_3") (pintype "passive"))
    )
    (net (code "61") (name "Net-(F2-Pad1)") (class "Default")
      (node (ref "F2") (pin "1") (pinfunction "1_1") (pintype "passive"))
      (node (ref "VD1") (pin "1") (pinfunction "1_1") (pintype "passive"))
    )
    (net (code "62") (name "Net-(KT5-Pad1)") (class "Default")
      (node (ref "KT5") (pin "1") (pinfunction "1_1") (pintype "passive"))
      (node (ref "R50") (pin "2") (pinfunction "2_2") (pintype "passive"))
      (node (ref "VD5") (pin "2") (pinfunction "2_2") (pintype "passive"))
      (node (ref "VD6") (pin "2") (pinfunction "2_2") (pintype "passive"))
    )
    (net (code "63") (name "Net-(R1-Pad2)") (class "Default")
      (node (ref "R1") (pin "2") (pinfunction "2_2") (pintype "passive"))
      (node (ref "R2") (pin "2") (pinfunction "2_2") (pintype "passive"))
      (node (ref "XP1") (pin "1") (pintype "passive"))
    )
    (net (code "64") (name "Net-(R13-Pad1)") (class "Default")
      (node (ref "R13") (pin "1") (pinfunction "1_1") (pintype "passive"))
      (node (ref "XP4") (pin "1") (pintype "passive"))
    )
    (net (code "65") (name "Net-(R13-Pad2)") (class "Default")
      (node (ref "R13") (pin "2") (pinfunction "2_2") (pintype "passive"))
      (node (ref "R18") (pin "1") (pinfunction "1_1") (pintype "passive"))
    )
    (net (code "66") (name "Net-(R14-Pad1)") (class "Default")
      (node (ref "R14") (pin "1") (pinfunction "1_1") (pintype "passive"))
      (node (ref "XP4") (pin "2") (pintype "passive"))
    )
    (net (code "67") (name "Net-(R14-Pad2)") (class "Default")
      (node (ref "R14") (pin "2") (pinfunction "2_2") (pintype "passive"))
      (node (ref "R19") (pin "1") (pinfunction "1_1") (pintype "passive"))
    )
    (net (code "68") (name "Net-(R15-Pad1)") (class "Default")
      (node (ref "R15") (pin "1") (pinfunction "1_1") (pintype "passive"))
      (node (ref "XP4") (pin "3") (pintype "passive"))
    )
    (net (code "69") (name "Net-(R15-Pad2)") (class "Default")
      (node (ref "R15") (pin "2") (pinfunction "2_2") (pintype "passive"))
      (node (ref "R20") (pin "1") (pinfunction "1_1") (pintype "passive"))
    )
    (net (code "70") (name "Net-(R16-Pad1)") (class "Default")
      (node (ref "R16") (pin "1") (pinfunction "1_1") (pintype "passive"))
      (node (ref "XP4") (pin "4") (pintype "passive"))
    )
    (net (code "71") (name "Net-(R16-Pad2)") (class "Default")
      (node (ref "R16") (pin "2") (pinfunction "2_2") (pintype "passive"))
      (node (ref "R21") (pin "1") (pinfunction "1_1") (pintype "passive"))
    )
    (net (code "72") (name "Net-(R22-Pad2)") (class "Default")
      (node (ref "R22") (pin "2") (pinfunction "2_2") (pintype "passive"))
      (node (ref "R23") (pin "2") (pinfunction "2_2") (pintype "passive"))
      (node (ref "R26") (pin "1") (pinfunction "1_1") (pintype "passive"))
    )
    (net (code "73") (name "Net-(R24-Pad2)") (class "Default")
      (node (ref "R24") (pin "2") (pinfunction "2_2") (pintype "passive"))
      (node (ref "VD3") (pin "2") (pinfunction "2_2") (pintype "passive"))
    )
    (net (code "74") (name "Net-(R34-Pad2)") (class "Default")
      (node (ref "R34") (pin "2") (pinfunction "2_2") (pintype "passive"))
      (node (ref "R36") (pin "3") (pinfunction "3_3") (pintype "passive"))
    )
    (net (code "75") (name "Net-(R35-Pad2)") (class "Default")
      (node (ref "R35") (pin "2") (pinfunction "2_2") (pintype "passive"))
      (node (ref "R36") (pin "1") (pinfunction "1_1") (pintype "passive"))
    )
    (net (code "76") (name "Net-(R38-Pad2)") (class "Default")
      (node (ref "R38") (pin "2") (pinfunction "2_2") (pintype "passive"))
      (node (ref "R42") (pin "3") (pinfunction "3_3") (pintype "passive"))
    )
    (net (code "77") (name "Net-(R39-Pad2)") (class "Default")
      (node (ref "R39") (pin "2") (pinfunction "2_2") (pintype "passive"))
      (node (ref "R42") (pin "1") (pinfunction "1_1") (pintype "passive"))
    )
    (net (code "78") (name "Net-(R51-Pad2)") (class "Default")
      (node (ref "R51") (pin "2") (pinfunction "2_2") (pintype "passive"))
      (node (ref "R53") (pin "2") (pinfunction "2_2") (pintype "passive"))
      (node (ref "R57") (pin "2") (pinfunction "2_2") (pintype "passive"))
    )
    (net (code "79") (name "Net-(R55-Pad2)") (class "Default")
      (node (ref "R55") (pin "2") (pinfunction "2_2") (pintype "passive"))
      (node (ref "R59") (pin "3") (pinfunction "3_3") (pintype "passive"))
    )
    (net (code "80") (name "Net-(R56-Pad2)") (class "Default")
      (node (ref "R56") (pin "2") (pinfunction "2_2") (pintype "passive"))
      (node (ref "R59") (pin "1") (pinfunction "1_1") (pintype "passive"))
    )
    (net (code "81") (name "Net-(R58-Pad2)") (class "Default")
      (node (ref "R58") (pin "2") (pinfunction "2_2") (pintype "passive"))
      (node (ref "R58") (pin "3") (pinfunction "3_3") (pintype "passive"))
      (node (ref "R63") (pin "2") (pinfunction "2_2") (pintype "passive"))
      (node (ref "R65") (pin "2") (pinfunction "2_2") (pintype "passive"))
      (node (ref "R65") (pin "3") (pinfunction "3_3") (pintype "passive"))
      (node (ref "XP10") (pin "1") (pintype "passive"))
    )
    (net (code "82") (name "Net-(R63-Pad1)") (class "Default")
      (node (ref "R63") (pin "1") (pinfunction "1_1") (pintype "passive"))
      (node (ref "R65") (pin "1") (pinfunction "1_1") (pintype "passive"))
      (node (ref "XP8") (pin "1") (pintype "passive"))
    )
    (net (code "83") (name "Net-(R64-Pad2)") (class "Default")
      (node (ref "R64") (pin "2") (pinfunction "2_2") (pintype "passive"))
      (node (ref "XP9") (pin "1") (pintype "passive"))
    )
    (net (code "84") (name "Net-(T1-Pad1)") (class "Default")
      (node (ref "T1") (pin "1") (pinfunction "1_1") (pintype "passive"))
      (node (ref "XP2") (pin "3") (pintype "passive"))
    )
    (net (code "85") (name "Net-(T1-Pad2)") (class "Default")
      (node (ref "T1") (pin "2") (pinfunction "2_2") (pintype "passive"))
      (node (ref "XP2") (pin "1") (pintype "passive"))
    )
    (net (code "86") (name "Net-(T1-Pad3)") (class "Default")
      (node (ref "T1") (pin "3") (pinfunction "3_3") (pintype "passive"))
      (node (ref "VD1") (pin "4") (pinfunction "4_4") (pintype "passive"))
    )
    (net (code "87") (name "Net-(T1-Pad6)") (class "Default")
      (node (ref "T1") (pin "6") (pinfunction "6_6") (pintype "passive"))
      (node (ref "VD1") (pin "2") (pinfunction "2_2") (pintype "passive"))
    )
    (net (code "88") (name "Net-(VT1-Pad1)") (class "Default")
      (node (ref "VT1") (pin "1") (pinfunction "1_1") (pintype "passive"))
      (node (ref "VT1") (pin "3") (pinfunction "3_3") (pintype "passive"))
      (node (ref "VT2") (pin "1") (pinfunction "1_1") (pintype "passive"))
      (node (ref "VT2") (pin "3") (pinfunction "3_3") (pintype "passive"))
    )
    (net (code "89") (name "Net-(VT3-G)") (class "Default")
      (node (ref "R44") (pin "2") (pinfunction "2_2") (pintype "passive"))
      (node (ref "VD2") (pin "1") (pinfunction "1_1") (pintype "passive"))
      (node (ref "VT3") (pin "3") (pinfunction "G_3") (pintype "passive"))
    )
    (net (code "90") (name "Net-(VT3-S)") (class "Default")
      (node (ref "R53") (pin "1") (pinfunction "1_1") (pintype "passive"))
      (node (ref "VT3") (pin "1") (pinfunction "S_1") (pintype "passive"))
    )
    (net (code "91") (name "Net-(VT4-G)") (class "Default")
      (node (ref "R60") (pin "1") (pinfunction "1_1") (pintype "passive"))
      (node (ref "VD4") (pin "1") (pinfunction "1_1") (pintype "passive"))
      (node (ref "VT4") (pin "3") (pinfunction "G_3") (pintype "passive"))
    )
    (net (code "92") (name "Net-(VT4-S)") (class "Default")
      (node (ref "R53") (pin "3") (pinfunction "3_3") (pintype "passive"))
      (node (ref "VT4") (pin "1") (pinfunction "S_1") (pintype "passive"))
    )
    (net (code "93") (name "unconnected-(DA2-CH6-Pad2)") (class "Default")
      (node (ref "DA2") (pin "2") (pinfunction "CH6_2") (pintype "passive"))
    )
    (net (code "94") (name "unconnected-(DA2-CH7-Pad4)") (class "Default")
      (node (ref "DA2") (pin "4") (pinfunction "CH7_4") (pintype "passive"))
    )
    (net (code "95") (name "unconnected-(XP2-Pad2)") (class "Default")
      (node (ref "XP2") (pin "2") (pintype "passive"))
    )
  )
)
